# counterMeterFixes.net
KiCad netlist of a schematic drawn in EAGLE
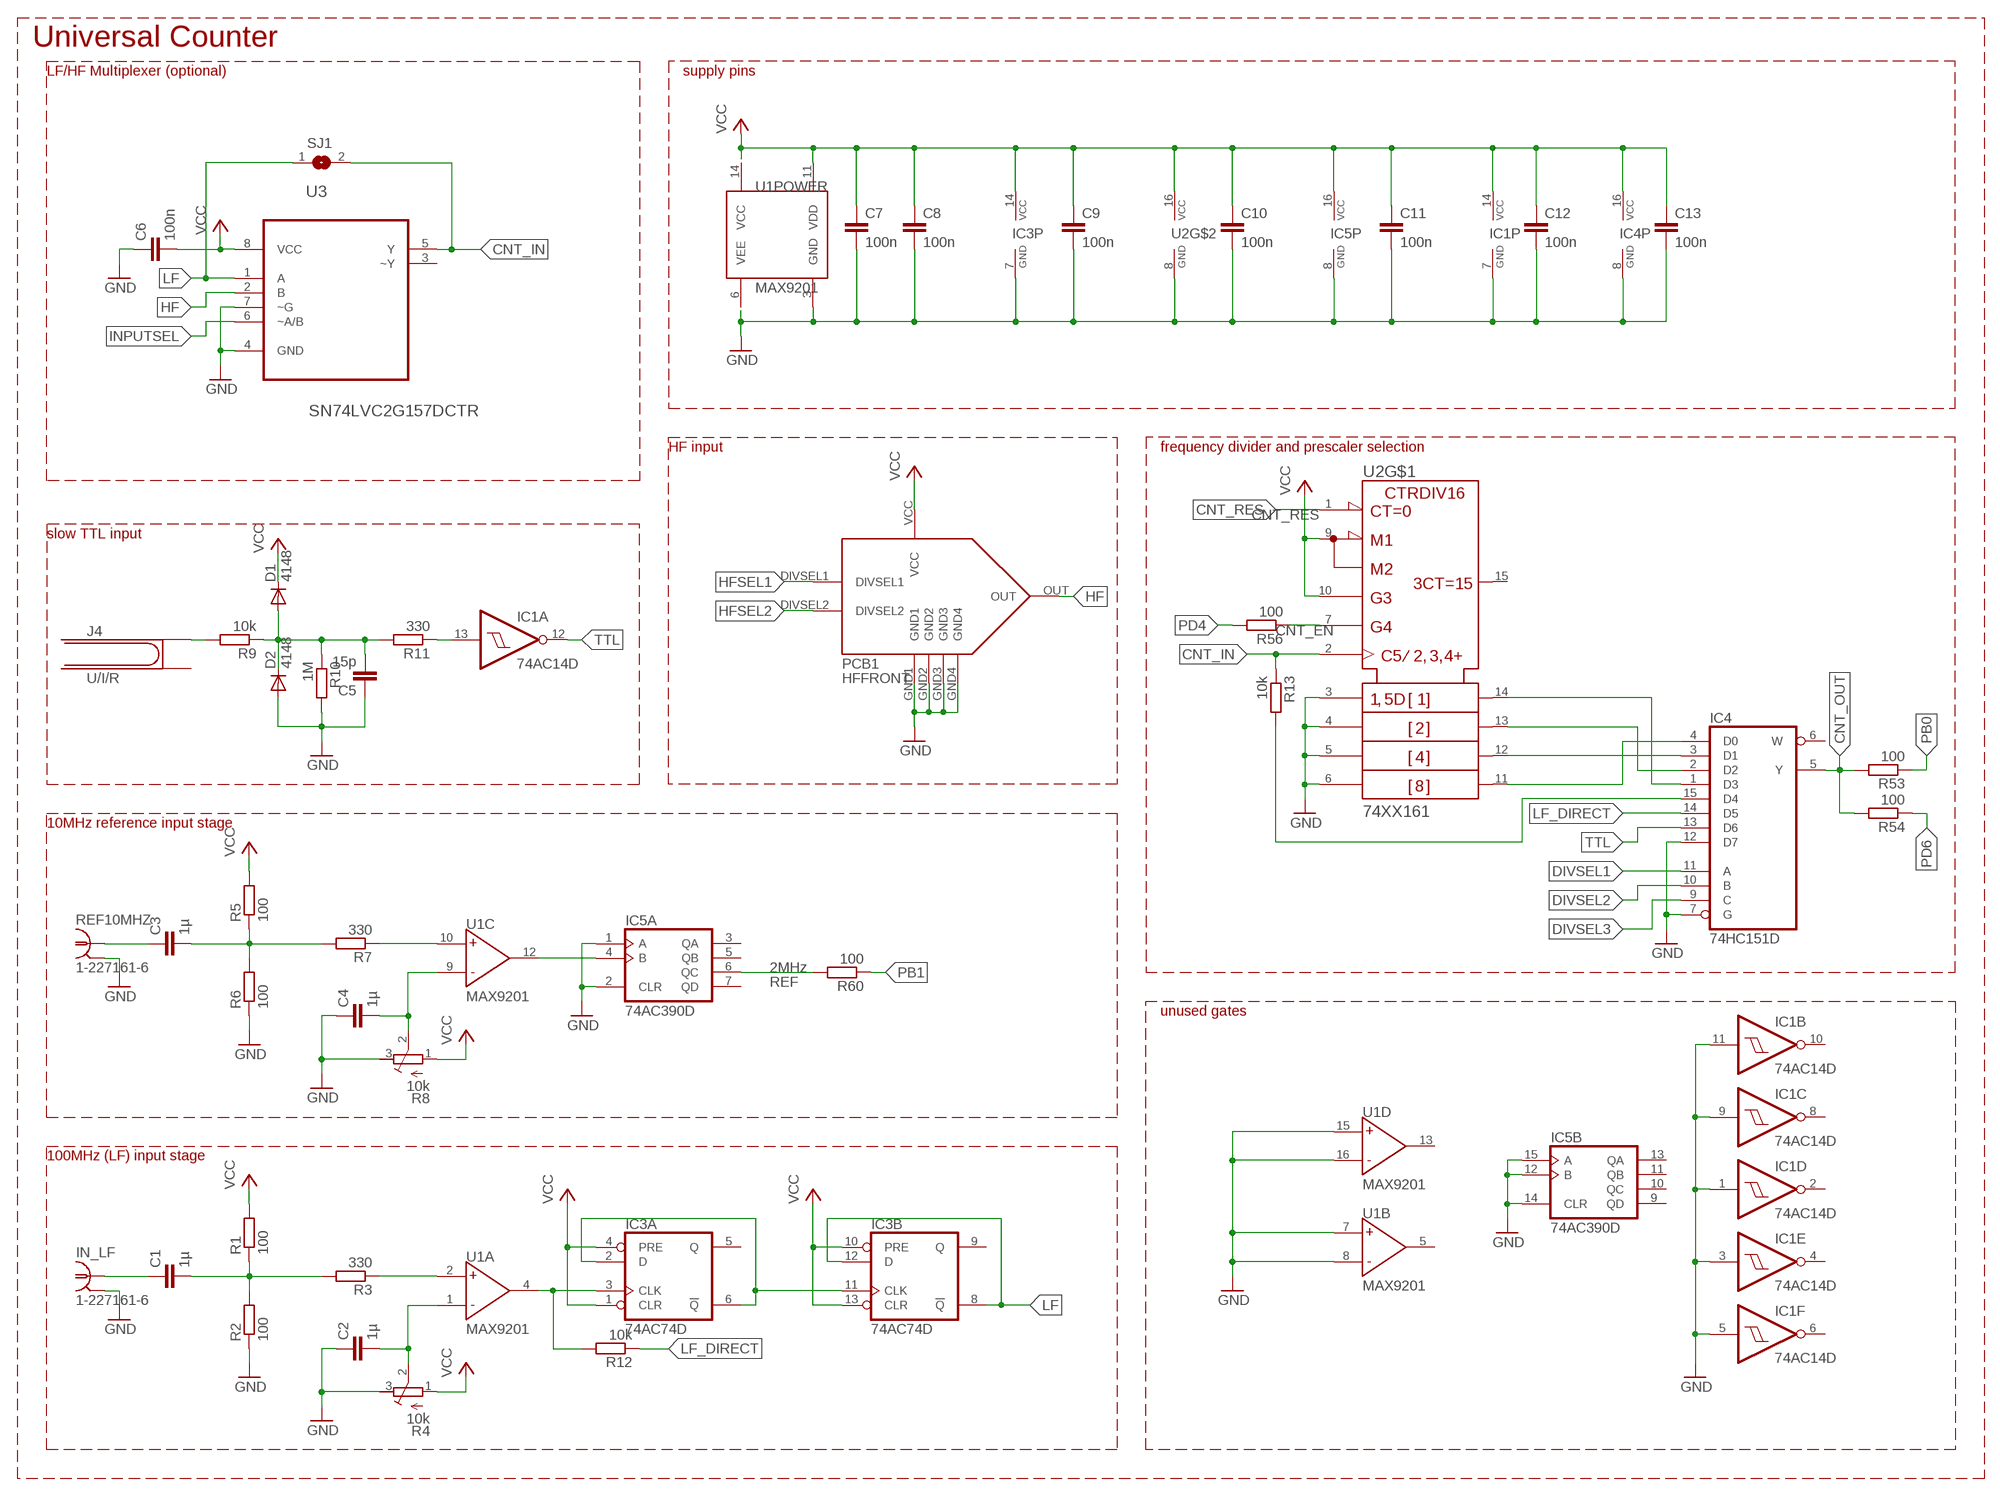
[diagram p0: schematic, sheet 1, part 1 of 2]
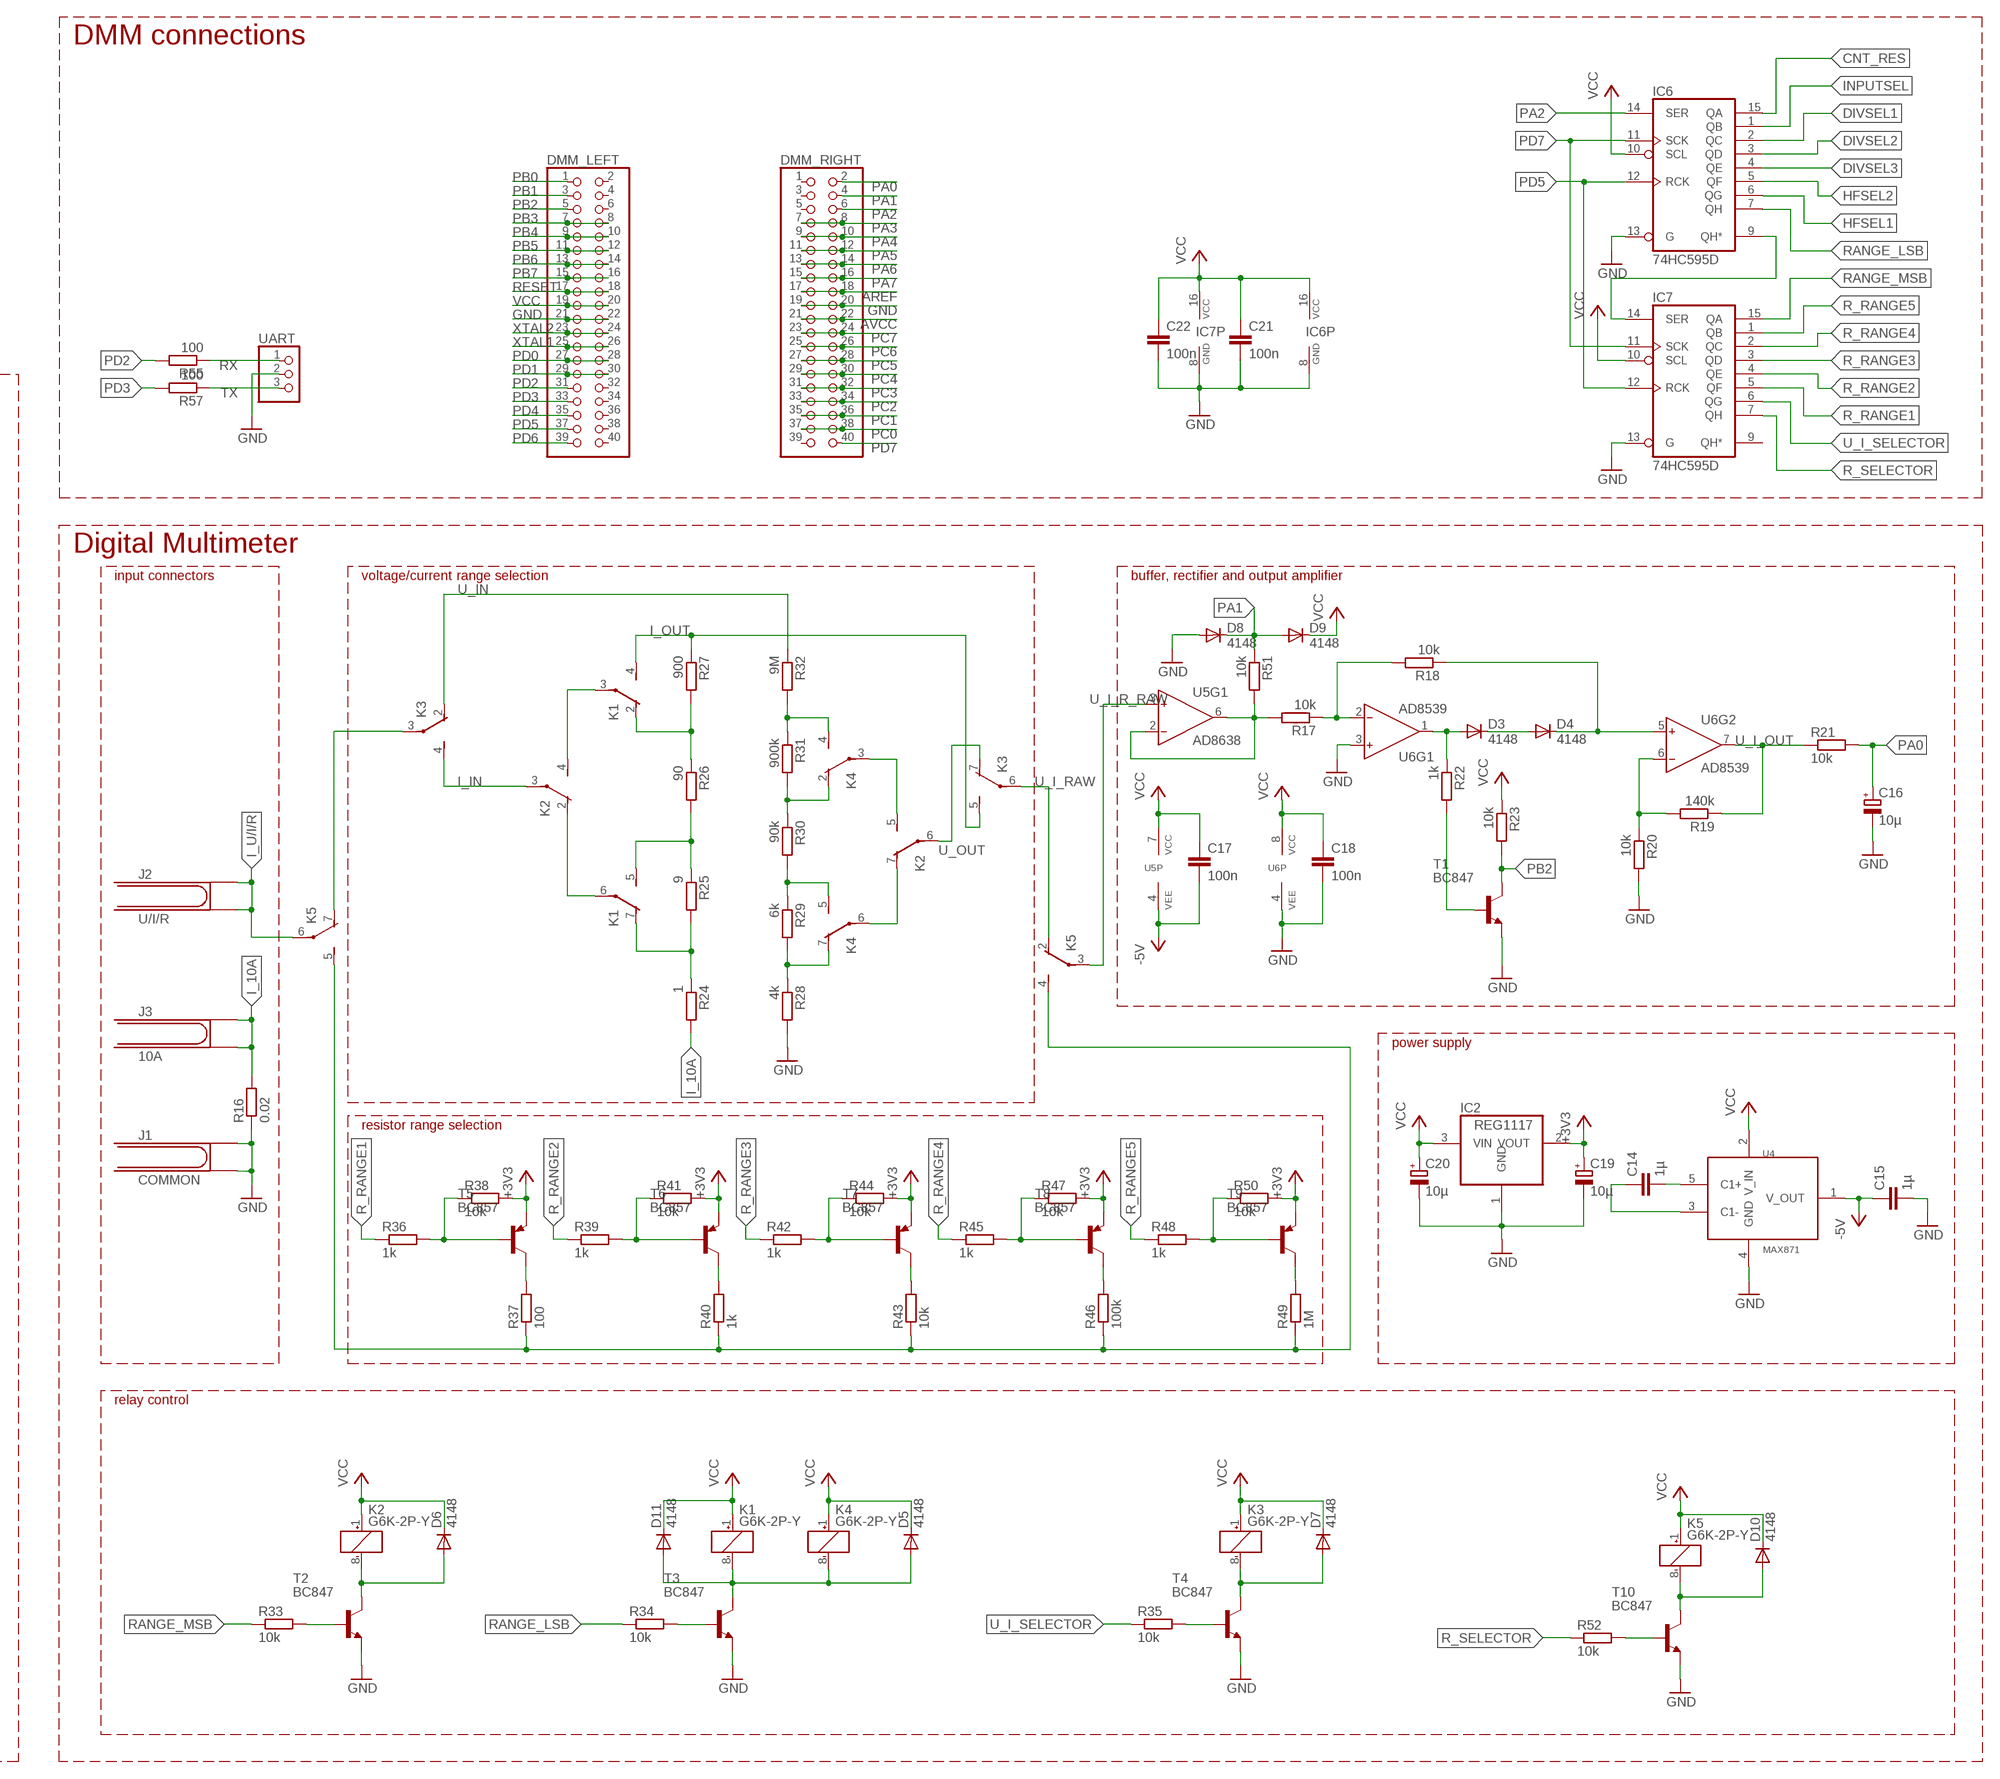
[diagram p1: schematic, sheet 1, part 2 of 2]

(export (version "E")
  (design (tool "Eeschema 10.0.6"))
  (components
    (comp (ref "C1")
      (value "1µ")
      (footprint "eagle-import:C0603")
      (libsource (lib "eagle-import") (part "C-EUC0603"))
    )
    (comp (ref "C2")
      (value "1µ")
      (footprint "eagle-import:C0603")
      (libsource (lib "eagle-import") (part "C-EUC0603"))
    )
    (comp (ref "C3")
      (value "1µ")
      (footprint "eagle-import:C0603")
      (libsource (lib "eagle-import") (part "C-EUC0603"))
    )
    (comp (ref "C4")
      (value "1µ")
      (footprint "eagle-import:C0603")
      (libsource (lib "eagle-import") (part "C-EUC0603"))
    )
    (comp (ref "C5")
      (value "15p")
      (footprint "eagle-import:C0603")
      (libsource (lib "eagle-import") (part "C-EUC0603"))
    )
    (comp (ref "C6")
      (value "100n")
      (footprint "eagle-import:C0603")
      (libsource (lib "eagle-import") (part "C-EUC0603"))
    )
    (comp (ref "C7")
      (value "100n")
      (footprint "eagle-import:C0603")
      (libsource (lib "eagle-import") (part "C-EUC0603"))
    )
    (comp (ref "C8")
      (value "100n")
      (footprint "eagle-import:C0603")
      (libsource (lib "eagle-import") (part "C-EUC0603"))
    )
    (comp (ref "C9")
      (value "100n")
      (footprint "eagle-import:C0603")
      (libsource (lib "eagle-import") (part "C-EUC0603"))
    )
    (comp (ref "C10")
      (value "100n")
      (footprint "eagle-import:C0603")
      (libsource (lib "eagle-import") (part "C-EUC0603"))
    )
    (comp (ref "C11")
      (value "100n")
      (footprint "eagle-import:C0603")
      (libsource (lib "eagle-import") (part "C-EUC0603"))
    )
    (comp (ref "C12")
      (value "100n")
      (footprint "eagle-import:C0603")
      (libsource (lib "eagle-import") (part "C-EUC0603"))
    )
    (comp (ref "C13")
      (value "100n")
      (footprint "eagle-import:C0603")
      (libsource (lib "eagle-import") (part "C-EUC0603"))
    )
    (comp (ref "C14")
      (value "1µ")
      (footprint "eagle-import:C0603")
      (libsource (lib "eagle-import") (part "C-EUC0603"))
    )
    (comp (ref "C15")
      (value "1µ")
      (footprint "eagle-import:C0603")
      (libsource (lib "eagle-import") (part "C-EUC0603"))
    )
    (comp (ref "C16")
      (value "10µ")
      (footprint "eagle-import:E2-5")
      (libsource (lib "eagle-import") (part "CPOL-EUE2-5"))
    )
    (comp (ref "C17")
      (value "100n")
      (footprint "eagle-import:C0603")
      (libsource (lib "eagle-import") (part "C-EUC0603"))
    )
    (comp (ref "C18")
      (value "100n")
      (footprint "eagle-import:C0603")
      (libsource (lib "eagle-import") (part "C-EUC0603"))
    )
    (comp (ref "C19")
      (value "10µ")
      (footprint "eagle-import:E2-5")
      (libsource (lib "eagle-import") (part "CPOL-EUE2-5"))
    )
    (comp (ref "C20")
      (value "10µ")
      (footprint "eagle-import:E2-5")
      (libsource (lib "eagle-import") (part "CPOL-EUE2-5"))
    )
    (comp (ref "C21")
      (value "100n")
      (footprint "eagle-import:C0603")
      (libsource (lib "eagle-import") (part "C-EUC0603"))
    )
    (comp (ref "C22")
      (value "100n")
      (footprint "eagle-import:C0603")
      (libsource (lib "eagle-import") (part "C-EUC0603"))
    )
    (comp (ref "D1")
      (value "4148")
      (footprint "eagle-import:SOD323-W")
      (libsource (lib "eagle-import") (part "DIODE-SOD323-W"))
    )
    (comp (ref "D2")
      (value "4148")
      (footprint "eagle-import:SOD323-W")
      (libsource (lib "eagle-import") (part "DIODE-SOD323-W"))
    )
    (comp (ref "D3")
      (value "4148")
      (footprint "eagle-import:SOD323-W")
      (libsource (lib "eagle-import") (part "DIODE-SOD323-W"))
    )
    (comp (ref "D4")
      (value "4148")
      (footprint "eagle-import:SOD323-W")
      (libsource (lib "eagle-import") (part "DIODE-SOD323-W"))
    )
    (comp (ref "D5")
      (value "4148")
      (footprint "eagle-import:SOD323-W")
      (libsource (lib "eagle-import") (part "DIODE-SOD323-W"))
    )
    (comp (ref "D6")
      (value "4148")
      (footprint "eagle-import:SOD323-W")
      (libsource (lib "eagle-import") (part "DIODE-SOD323-W"))
    )
    (comp (ref "D7")
      (value "4148")
      (footprint "eagle-import:SOD323-W")
      (libsource (lib "eagle-import") (part "DIODE-SOD323-W"))
    )
    (comp (ref "D8")
      (value "4148")
      (footprint "eagle-import:SOD323-W")
      (libsource (lib "eagle-import") (part "DIODE-SOD323-W"))
    )
    (comp (ref "D9")
      (value "4148")
      (footprint "eagle-import:SOD323-W")
      (libsource (lib "eagle-import") (part "DIODE-SOD323-W"))
    )
    (comp (ref "D10")
      (value "4148")
      (footprint "eagle-import:SOD323-W")
      (libsource (lib "eagle-import") (part "DIODE-SOD323-W"))
    )
    (comp (ref "D11")
      (value "4148")
      (footprint "eagle-import:SOD323-W")
      (libsource (lib "eagle-import") (part "DIODE-SOD323-W"))
    )
    (comp (ref "DMM_LEFT")
      (value "PINHD-2X20")
      (footprint "eagle-import:2X20")
      (libsource (lib "eagle-import") (part "PINHD-2X20"))
    )
    (comp (ref "DMM_RIGHT")
      (value "PINHD-2X20")
      (footprint "eagle-import:2X20")
      (libsource (lib "eagle-import") (part "PINHD-2X20"))
    )
    (comp (ref "IC1")
      (value "74AC14D")
      (footprint "eagle-import:SO14")
      (libsource (lib "eagle-import") (part "7414DAC"))
    )
    (comp (ref "IC2")
      (value "REG1117")
      (footprint "eagle-import:SOT223")
      (libsource (lib "eagle-import") (part "REG1117"))
    )
    (comp (ref "IC3")
      (value "74AC74D")
      (footprint "eagle-import:SO14")
      (libsource (lib "eagle-import") (part "7474DAC"))
    )
    (comp (ref "IC4")
      (value "74HC151D")
      (footprint "eagle-import:SO16")
      (libsource (lib "eagle-import") (part "74151DHC"))
    )
    (comp (ref "IC5")
      (value "74AC390D")
      (footprint "eagle-import:SO16")
      (libsource (lib "eagle-import") (part "74390DAC"))
    )
    (comp (ref "IC6")
      (value "74HC595D")
      (footprint "eagle-import:SO16")
      (libsource (lib "eagle-import") (part "74595DHC"))
    )
    (comp (ref "IC7")
      (value "74HC595D")
      (footprint "eagle-import:SO16")
      (libsource (lib "eagle-import") (part "74595DHC"))
    )
    (comp (ref "IN_LF")
      (value "1-227161-6")
      (footprint "eagle-import:AMP_227161")
      (fields (field (name "MF") "TYCO ELECTRONICS"))
      (libsource (lib "eagle-import") (part "?2271611--6"))
    )
    (comp (ref "J1")
      (value "COMMON")
      (footprint "eagle-import:4MMJACK")
      (libsource (lib "eagle-import") (part "4MMJACK"))
    )
    (comp (ref "J2")
      (value "U/I/R")
      (footprint "eagle-import:4MMJACK")
      (libsource (lib "eagle-import") (part "4MMJACK"))
    )
    (comp (ref "J3")
      (value "10A")
      (footprint "eagle-import:4MMJACK")
      (libsource (lib "eagle-import") (part "4MMJACK"))
    )
    (comp (ref "J4")
      (value "U/I/R")
      (footprint "eagle-import:4MMJACK")
      (libsource (lib "eagle-import") (part "4MMJACK"))
    )
    (comp (ref "K1")
      (value "G6K-2P-Y")
      (footprint "eagle-import:G6K-2P-Y")
      (fields (field (name "MF") "OMRON COMPONENTS USA") (field (name "MPN") "G6K-2P-Y DC12"))
      (libsource (lib "eagle-import") (part "G6K-2P-Y"))
    )
    (comp (ref "K2")
      (value "G6K-2P-Y")
      (footprint "eagle-import:G6K-2P-Y")
      (fields (field (name "MF") "OMRON COMPONENTS USA") (field (name "MPN") "G6K-2P-Y DC12"))
      (libsource (lib "eagle-import") (part "G6K-2P-Y"))
    )
    (comp (ref "K3")
      (value "G6K-2P-Y")
      (footprint "eagle-import:G6K-2P-Y")
      (fields (field (name "MF") "OMRON COMPONENTS USA") (field (name "MPN") "G6K-2P-Y DC12"))
      (libsource (lib "eagle-import") (part "G6K-2P-Y"))
    )
    (comp (ref "K4")
      (value "G6K-2P-Y")
      (footprint "eagle-import:G6K-2P-Y")
      (fields (field (name "MF") "OMRON COMPONENTS USA") (field (name "MPN") "G6K-2P-Y DC12"))
      (libsource (lib "eagle-import") (part "G6K-2P-Y"))
    )
    (comp (ref "K5")
      (value "G6K-2P-Y")
      (footprint "eagle-import:G6K-2P-Y")
      (fields (field (name "MF") "OMRON COMPONENTS USA") (field (name "MPN") "G6K-2P-Y DC12"))
      (libsource (lib "eagle-import") (part "G6K-2P-Y"))
    )
    (comp (ref "PCB1")
      (value "HFFRONT")
      (footprint "eagle-import:HFFRONT")
      (libsource (lib "eagle-import") (part "HFFRONT"))
    )
    (comp (ref "R1")
      (value "100")
      (footprint "eagle-import:R0603")
      (libsource (lib "eagle-import") (part "R-EU_R0603"))
    )
    (comp (ref "R2")
      (value "100")
      (footprint "eagle-import:R0603")
      (libsource (lib "eagle-import") (part "R-EU_R0603"))
    )
    (comp (ref "R3")
      (value "330")
      (footprint "eagle-import:R0603")
      (libsource (lib "eagle-import") (part "R-EU_R0603"))
    )
    (comp (ref "R4")
      (value "10k")
      (footprint "eagle-import:RTRIM64W")
      (libsource (lib "eagle-import") (part "R-TRIMM64W"))
    )
    (comp (ref "R5")
      (value "100")
      (footprint "eagle-import:R0603")
      (libsource (lib "eagle-import") (part "R-EU_R0603"))
    )
    (comp (ref "R6")
      (value "100")
      (footprint "eagle-import:R0603")
      (libsource (lib "eagle-import") (part "R-EU_R0603"))
    )
    (comp (ref "R7")
      (value "330")
      (footprint "eagle-import:R0603")
      (libsource (lib "eagle-import") (part "R-EU_R0603"))
    )
    (comp (ref "R8")
      (value "10k")
      (footprint "eagle-import:RTRIM64W")
      (libsource (lib "eagle-import") (part "R-TRIMM64W"))
    )
    (comp (ref "R9")
      (value "10k")
      (footprint "eagle-import:R0603")
      (libsource (lib "eagle-import") (part "R-EU_R0603"))
    )
    (comp (ref "R10")
      (value "1M")
      (footprint "eagle-import:R0603")
      (libsource (lib "eagle-import") (part "R-EU_R0603"))
    )
    (comp (ref "R11")
      (value "330")
      (footprint "eagle-import:R0603")
      (libsource (lib "eagle-import") (part "R-EU_R0603"))
    )
    (comp (ref "R12")
      (value "10k")
      (footprint "eagle-import:R0603")
      (libsource (lib "eagle-import") (part "R-EU_R0603"))
    )
    (comp (ref "R13")
      (value "10k")
      (footprint "eagle-import:R0603")
      (libsource (lib "eagle-import") (part "R-EU_R0603"))
    )
    (comp (ref "R16")
      (value "0.02")
      (footprint "eagle-import:R2512")
      (libsource (lib "eagle-import") (part "R-EU_R2512"))
    )
    (comp (ref "R17")
      (value "10k")
      (footprint "eagle-import:R0603")
      (libsource (lib "eagle-import") (part "R-EU_R0603"))
    )
    (comp (ref "R18")
      (value "10k")
      (footprint "eagle-import:R0603")
      (libsource (lib "eagle-import") (part "R-EU_R0603"))
    )
    (comp (ref "R19")
      (value "140k")
      (footprint "eagle-import:R0603")
      (libsource (lib "eagle-import") (part "R-EU_R0603"))
    )
    (comp (ref "R20")
      (value "10k")
      (footprint "eagle-import:R0603")
      (libsource (lib "eagle-import") (part "R-EU_R0603"))
    )
    (comp (ref "R21")
      (value "10k")
      (footprint "eagle-import:R0603")
      (libsource (lib "eagle-import") (part "R-EU_R0603"))
    )
    (comp (ref "R22")
      (value "1k")
      (footprint "eagle-import:R0603")
      (libsource (lib "eagle-import") (part "R-EU_R0603"))
    )
    (comp (ref "R23")
      (value "10k")
      (footprint "eagle-import:R0603")
      (libsource (lib "eagle-import") (part "R-EU_R0603"))
    )
    (comp (ref "R24")
      (value "1")
      (footprint "eagle-import:R0603")
      (libsource (lib "eagle-import") (part "R-EU_R0603"))
    )
    (comp (ref "R25")
      (value "9")
      (footprint "eagle-import:R0603")
      (libsource (lib "eagle-import") (part "R-EU_R0603"))
    )
    (comp (ref "R26")
      (value "90")
      (footprint "eagle-import:R0603")
      (libsource (lib "eagle-import") (part "R-EU_R0603"))
    )
    (comp (ref "R27")
      (value "900")
      (footprint "eagle-import:R0603")
      (libsource (lib "eagle-import") (part "R-EU_R0603"))
    )
    (comp (ref "R28")
      (value "4k")
      (footprint "eagle-import:R0603")
      (libsource (lib "eagle-import") (part "R-EU_R0603"))
    )
    (comp (ref "R29")
      (value "6k")
      (footprint "eagle-import:R0603")
      (libsource (lib "eagle-import") (part "R-EU_R0603"))
    )
    (comp (ref "R30")
      (value "90k")
      (footprint "eagle-import:R0603")
      (libsource (lib "eagle-import") (part "R-EU_R0603"))
    )
    (comp (ref "R31")
      (value "900k")
      (footprint "eagle-import:R0603")
      (libsource (lib "eagle-import") (part "R-EU_R0603"))
    )
    (comp (ref "R32")
      (value "9M")
      (footprint "eagle-import:R0603")
      (libsource (lib "eagle-import") (part "R-EU_R0603"))
    )
    (comp (ref "R33")
      (value "10k")
      (footprint "eagle-import:R0603")
      (libsource (lib "eagle-import") (part "R-EU_R0603"))
    )
    (comp (ref "R34")
      (value "10k")
      (footprint "eagle-import:R0603")
      (libsource (lib "eagle-import") (part "R-EU_R0603"))
    )
    (comp (ref "R35")
      (value "10k")
      (footprint "eagle-import:R0603")
      (libsource (lib "eagle-import") (part "R-EU_R0603"))
    )
    (comp (ref "R36")
      (value "1k")
      (footprint "eagle-import:R0603")
      (libsource (lib "eagle-import") (part "R-EU_R0603"))
    )
    (comp (ref "R37")
      (value "100")
      (footprint "eagle-import:R0603")
      (libsource (lib "eagle-import") (part "R-EU_R0603"))
    )
    (comp (ref "R38")
      (value "10k")
      (footprint "eagle-import:R0603")
      (libsource (lib "eagle-import") (part "R-EU_R0603"))
    )
    (comp (ref "R39")
      (value "1k")
      (footprint "eagle-import:R0603")
      (libsource (lib "eagle-import") (part "R-EU_R0603"))
    )
    (comp (ref "R40")
      (value "1k")
      (footprint "eagle-import:R0603")
      (libsource (lib "eagle-import") (part "R-EU_R0603"))
    )
    (comp (ref "R41")
      (value "10k")
      (footprint "eagle-import:R0603")
      (libsource (lib "eagle-import") (part "R-EU_R0603"))
    )
    (comp (ref "R42")
      (value "1k")
      (footprint "eagle-import:R0603")
      (libsource (lib "eagle-import") (part "R-EU_R0603"))
    )
    (comp (ref "R43")
      (value "10k")
      (footprint "eagle-import:R0603")
      (libsource (lib "eagle-import") (part "R-EU_R0603"))
    )
    (comp (ref "R44")
      (value "10k")
      (footprint "eagle-import:R0603")
      (libsource (lib "eagle-import") (part "R-EU_R0603"))
    )
    (comp (ref "R45")
      (value "1k")
      (footprint "eagle-import:R0603")
      (libsource (lib "eagle-import") (part "R-EU_R0603"))
    )
    (comp (ref "R46")
      (value "100k")
      (footprint "eagle-import:R0603")
      (libsource (lib "eagle-import") (part "R-EU_R0603"))
    )
    (comp (ref "R47")
      (value "10k")
      (footprint "eagle-import:R0603")
      (libsource (lib "eagle-import") (part "R-EU_R0603"))
    )
    (comp (ref "R48")
      (value "1k")
      (footprint "eagle-import:R0603")
      (libsource (lib "eagle-import") (part "R-EU_R0603"))
    )
    (comp (ref "R49")
      (value "1M")
      (footprint "eagle-import:R0603")
      (libsource (lib "eagle-import") (part "R-EU_R0603"))
    )
    (comp (ref "R50")
      (value "10k")
      (footprint "eagle-import:R0603")
      (libsource (lib "eagle-import") (part "R-EU_R0603"))
    )
    (comp (ref "R51")
      (value "10k")
      (footprint "eagle-import:R0603")
      (libsource (lib "eagle-import") (part "R-EU_R0603"))
    )
    (comp (ref "R52")
      (value "10k")
      (footprint "eagle-import:R0603")
      (libsource (lib "eagle-import") (part "R-EU_R0603"))
    )
    (comp (ref "R53")
      (value "100")
      (footprint "eagle-import:R0603")
      (libsource (lib "eagle-import") (part "R-EU_R0603"))
    )
    (comp (ref "R54")
      (value "100")
      (footprint "eagle-import:R0603")
      (libsource (lib "eagle-import") (part "R-EU_R0603"))
    )
    (comp (ref "R55")
      (value "100")
      (footprint "eagle-import:R0603")
      (libsource (lib "eagle-import") (part "R-EU_R0603"))
    )
    (comp (ref "R56")
      (value "100")
      (footprint "eagle-import:R0603")
      (libsource (lib "eagle-import") (part "R-EU_R0603"))
    )
    (comp (ref "R57")
      (value "100")
      (footprint "eagle-import:R0603")
      (libsource (lib "eagle-import") (part "R-EU_R0603"))
    )
    (comp (ref "R60")
      (value "100")
      (footprint "eagle-import:R0603")
      (libsource (lib "eagle-import") (part "R-EU_R0603"))
    )
    (comp (ref "REF10MHZ")
      (value "1-227161-6")
      (footprint "eagle-import:AMP_227161")
      (fields (field (name "MF") "TYCO ELECTRONICS"))
      (libsource (lib "eagle-import") (part "?2271611--6"))
    )
    (comp (ref "SJ1") (value "SJ") (footprint "eagle-import:SJ") (libsource (lib "eagle-import") (part "SJ")))
    (comp (ref "T1")
      (value "BC847")
      (footprint "eagle-import:SOT23")
      (libsource (lib "eagle-import") (part "BC847"))
    )
    (comp (ref "T2")
      (value "BC847")
      (footprint "eagle-import:SOT23")
      (libsource (lib "eagle-import") (part "BC847"))
    )
    (comp (ref "T3")
      (value "BC847")
      (footprint "eagle-import:SOT23")
      (libsource (lib "eagle-import") (part "BC847"))
    )
    (comp (ref "T4")
      (value "BC847")
      (footprint "eagle-import:SOT23")
      (libsource (lib "eagle-import") (part "BC847"))
    )
    (comp (ref "T5")
      (value "BC857")
      (footprint "eagle-import:SOT23-BEC")
      (libsource (lib "eagle-import") (part "-PNP-SOT23-BECBC857C"))
    )
    (comp (ref "T6")
      (value "BC857")
      (footprint "eagle-import:SOT23-BEC")
      (libsource (lib "eagle-import") (part "-PNP-SOT23-BECBC857C"))
    )
    (comp (ref "T7")
      (value "BC857")
      (footprint "eagle-import:SOT23-BEC")
      (libsource (lib "eagle-import") (part "-PNP-SOT23-BECBC857C"))
    )
    (comp (ref "T8")
      (value "BC857")
      (footprint "eagle-import:SOT23-BEC")
      (libsource (lib "eagle-import") (part "-PNP-SOT23-BECBC857C"))
    )
    (comp (ref "T9")
      (value "BC857")
      (footprint "eagle-import:SOT23-BEC")
      (libsource (lib "eagle-import") (part "-PNP-SOT23-BECBC857C"))
    )
    (comp (ref "T10")
      (value "BC847")
      (footprint "eagle-import:SOT23")
      (libsource (lib "eagle-import") (part "BC847"))
    )
    (comp (ref "U1")
      (value "MAX9201")
      (footprint "eagle-import:SOIC16")
      (libsource (lib "eagle-import") (part "MAX9201"))
    )
    (comp (ref "U2")
      (value "74XX161")
      (footprint "eagle-import:SOIC16")
      (libsource (lib "eagle-import") (part "74XX161"))
    )
    (comp (ref "U3")
      (value "SN74LVC2G157DCTR")
      (footprint "eagle-import:SOP65P400X130-8N")
      (libsource (lib "eagle-import") (part "SN74LVC2G157DCTR"))
    )
    (comp (ref "U4")
      (value "MAX871")
      (footprint "eagle-import:SOT23-5")
      (libsource (lib "eagle-import") (part "MAX871"))
    )
    (comp (ref "U5")
      (value "AD8638")
      (footprint "eagle-import:SOIC8")
      (libsource (lib "eagle-import") (part "AD8638"))
    )
    (comp (ref "U6")
      (value "AD8539")
      (footprint "eagle-import:SOIC8")
      (libsource (lib "eagle-import") (part "AD8539"))
    )
    (comp (ref "UART")
      (value "PINHD-1X3")
      (footprint "eagle-import:1X03")
      (libsource (lib "eagle-import") (part "PINHD-1X3"))
    )
  )
  (nets
    (net (code "1") (name "+3V3") (class "Default")
      (node (ref "C19") (pin "+") (pinfunction "+_+") (pintype "passive"))
      (node (ref "IC2") (pin "2") (pinfunction "VOUT_2") (pintype "output"))
      (node (ref "R38") (pin "2") (pinfunction "2_2") (pintype "passive"))
      (node (ref "R41") (pin "2") (pinfunction "2_2") (pintype "passive"))
      (node (ref "R44") (pin "2") (pinfunction "2_2") (pintype "passive"))
      (node (ref "R47") (pin "2") (pinfunction "2_2") (pintype "passive"))
      (node (ref "R50") (pin "2") (pinfunction "2_2") (pintype "passive"))
      (node (ref "T5") (pin "E") (pinfunction "E_E") (pintype "passive"))
      (node (ref "T6") (pin "E") (pinfunction "E_E") (pintype "passive"))
      (node (ref "T7") (pin "E") (pinfunction "E_E") (pintype "passive"))
      (node (ref "T8") (pin "E") (pinfunction "E_E") (pintype "passive"))
      (node (ref "T9") (pin "E") (pinfunction "E_E") (pintype "passive"))
    )
    (net (code "2") (name "-5V") (class "Default")
      (node (ref "C15") (pin "1") (pinfunction "1_1") (pintype "passive"))
      (node (ref "C17") (pin "2") (pinfunction "2_2") (pintype "passive"))
      (node (ref "U4") (pin "1") (pinfunction "V_OUT_1") (pintype "bidirectional"))
      (node (ref "U5") (pin "4") (pinfunction "VEE_4") (pintype "bidirectional"))
    )
    (net (code "3") (name "/AREF") (class "Default")
      (node (ref "DMM_RIGHT") (pin "17") (pinfunction "17_17") (pintype "passive"))
      (node (ref "DMM_RIGHT") (pin "18") (pinfunction "18_18") (pintype "passive"))
    )
    (net (code "4") (name "/AVCC") (class "Default")
      (node (ref "DMM_RIGHT") (pin "21") (pinfunction "21_21") (pintype "passive"))
      (node (ref "DMM_RIGHT") (pin "22") (pinfunction "22_22") (pintype "passive"))
    )
    (net (code "5") (name "/CNT_EN") (class "Default")
      (node (ref "R56") (pin "1") (pinfunction "1_1") (pintype "passive"))
      (node (ref "U2") (pin "7") (pinfunction "ENP_7") (pintype "input"))
    )
    (net (code "6") (name "/I_IN") (class "Default")
      (node (ref "K2") (pin "3") (pinfunction "P_3") (pintype "passive"))
      (node (ref "K3") (pin "4") (pinfunction "S_4") (pintype "passive"))
    )
    (net (code "7") (name "/I_OUT") (class "Default")
      (node (ref "K1") (pin "4") (pinfunction "S_4") (pintype "passive"))
      (node (ref "K3") (pin "5") (pinfunction "S_5") (pintype "passive"))
      (node (ref "R27") (pin "1") (pinfunction "1_1") (pintype "passive"))
    )
    (net (code "8") (name "/PA3") (class "Default")
      (node (ref "DMM_RIGHT") (pin "7") (pinfunction "7_7") (pintype "passive"))
      (node (ref "DMM_RIGHT") (pin "8") (pinfunction "8_8") (pintype "passive"))
    )
    (net (code "9") (name "/PA4") (class "Default")
      (node (ref "DMM_RIGHT") (pin "10") (pinfunction "10_10") (pintype "passive"))
      (node (ref "DMM_RIGHT") (pin "9") (pinfunction "9_9") (pintype "passive"))
    )
    (net (code "10") (name "/PA5") (class "Default")
      (node (ref "DMM_RIGHT") (pin "11") (pinfunction "11_11") (pintype "passive"))
      (node (ref "DMM_RIGHT") (pin "12") (pinfunction "12_12") (pintype "passive"))
    )
    (net (code "11") (name "/PA6") (class "Default")
      (node (ref "DMM_RIGHT") (pin "13") (pinfunction "13_13") (pintype "passive"))
      (node (ref "DMM_RIGHT") (pin "14") (pinfunction "14_14") (pintype "passive"))
    )
    (net (code "12") (name "/PA7") (class "Default")
      (node (ref "DMM_RIGHT") (pin "15") (pinfunction "15_15") (pintype "passive"))
      (node (ref "DMM_RIGHT") (pin "16") (pinfunction "16_16") (pintype "passive"))
    )
    (net (code "13") (name "/PB3") (class "Default")
      (node (ref "DMM_LEFT") (pin "7") (pinfunction "7_7") (pintype "passive"))
      (node (ref "DMM_LEFT") (pin "8") (pinfunction "8_8") (pintype "passive"))
    )
    (net (code "14") (name "/PB4") (class "Default")
      (node (ref "DMM_LEFT") (pin "10") (pinfunction "10_10") (pintype "passive"))
      (node (ref "DMM_LEFT") (pin "9") (pinfunction "9_9") (pintype "passive"))
    )
    (net (code "15") (name "/PB5") (class "Default")
      (node (ref "DMM_LEFT") (pin "11") (pinfunction "11_11") (pintype "passive"))
      (node (ref "DMM_LEFT") (pin "12") (pinfunction "12_12") (pintype "passive"))
    )
    (net (code "16") (name "/PB6") (class "Default")
      (node (ref "DMM_LEFT") (pin "13") (pinfunction "13_13") (pintype "passive"))
      (node (ref "DMM_LEFT") (pin "14") (pinfunction "14_14") (pintype "passive"))
    )
    (net (code "17") (name "/PB7") (class "Default")
      (node (ref "DMM_LEFT") (pin "15") (pinfunction "15_15") (pintype "passive"))
      (node (ref "DMM_LEFT") (pin "16") (pinfunction "16_16") (pintype "passive"))
    )
    (net (code "18") (name "/PC0") (class "Default")
      (node (ref "DMM_RIGHT") (pin "37") (pinfunction "37_37") (pintype "passive"))
      (node (ref "DMM_RIGHT") (pin "38") (pinfunction "38_38") (pintype "passive"))
    )
    (net (code "19") (name "/PC1") (class "Default")
      (node (ref "DMM_RIGHT") (pin "35") (pinfunction "35_35") (pintype "passive"))
      (node (ref "DMM_RIGHT") (pin "36") (pinfunction "36_36") (pintype "passive"))
    )
    (net (code "20") (name "/PC2") (class "Default")
      (node (ref "DMM_RIGHT") (pin "33") (pinfunction "33_33") (pintype "passive"))
      (node (ref "DMM_RIGHT") (pin "34") (pinfunction "34_34") (pintype "passive"))
    )
    (net (code "21") (name "/PC3") (class "Default")
      (node (ref "DMM_RIGHT") (pin "31") (pinfunction "31_31") (pintype "passive"))
      (node (ref "DMM_RIGHT") (pin "32") (pinfunction "32_32") (pintype "passive"))
    )
    (net (code "22") (name "/PC4") (class "Default")
      (node (ref "DMM_RIGHT") (pin "29") (pinfunction "29_29") (pintype "passive"))
      (node (ref "DMM_RIGHT") (pin "30") (pinfunction "30_30") (pintype "passive"))
    )
    (net (code "23") (name "/PC5") (class "Default")
      (node (ref "DMM_RIGHT") (pin "27") (pinfunction "27_27") (pintype "passive"))
      (node (ref "DMM_RIGHT") (pin "28") (pinfunction "28_28") (pintype "passive"))
    )
    (net (code "24") (name "/PC6") (class "Default")
      (node (ref "DMM_RIGHT") (pin "25") (pinfunction "25_25") (pintype "passive"))
      (node (ref "DMM_RIGHT") (pin "26") (pinfunction "26_26") (pintype "passive"))
    )
    (net (code "25") (name "/PC7") (class "Default")
      (node (ref "DMM_RIGHT") (pin "23") (pinfunction "23_23") (pintype "passive"))
      (node (ref "DMM_RIGHT") (pin "24") (pinfunction "24_24") (pintype "passive"))
    )
    (net (code "26") (name "/PD0") (class "Default")
      (node (ref "DMM_LEFT") (pin "27") (pinfunction "27_27") (pintype "passive"))
      (node (ref "DMM_LEFT") (pin "28") (pinfunction "28_28") (pintype "passive"))
    )
    (net (code "27") (name "/PD1") (class "Default")
      (node (ref "DMM_LEFT") (pin "29") (pinfunction "29_29") (pintype "passive"))
      (node (ref "DMM_LEFT") (pin "30") (pinfunction "30_30") (pintype "passive"))
    )
    (net (code "28") (name "/REF") (class "Default")
      (node (ref "IC5") (pin "6") (pinfunction "QC_6") (pintype "output"))
      (node (ref "R60") (pin "2") (pinfunction "2_2") (pintype "passive"))
    )
    (net (code "29") (name "/RESET") (class "Default")
      (node (ref "DMM_LEFT") (pin "17") (pinfunction "17_17") (pintype "passive"))
      (node (ref "DMM_LEFT") (pin "18") (pinfunction "18_18") (pintype "passive"))
    )
    (net (code "30") (name "/RX") (class "Default")
      (node (ref "R55") (pin "1") (pinfunction "1_1") (pintype "passive"))
      (node (ref "UART") (pin "1") (pinfunction "1_1") (pintype "passive"))
    )
    (net (code "31") (name "/TX") (class "Default")
      (node (ref "R57") (pin "1") (pinfunction "1_1") (pintype "passive"))
      (node (ref "UART") (pin "3") (pinfunction "3_3") (pintype "passive"))
    )
    (net (code "32") (name "/U_IN") (class "Default")
      (node (ref "K3") (pin "2") (pinfunction "O_2") (pintype "passive"))
      (node (ref "R32") (pin "1") (pinfunction "1_1") (pintype "passive"))
    )
    (net (code "33") (name "/U_I_OUT") (class "Default")
      (node (ref "R19") (pin "1") (pinfunction "1_1") (pintype "passive"))
      (node (ref "R21") (pin "1") (pinfunction "1_1") (pintype "passive"))
      (node (ref "U6") (pin "7") (pinfunction "OUT_7") (pintype "output"))
    )
    (net (code "34") (name "/U_I_RAW") (class "Default")
      (node (ref "K3") (pin "6") (pinfunction "P_6") (pintype "passive"))
      (node (ref "K5") (pin "2") (pinfunction "O_2") (pintype "passive"))
    )
    (net (code "35") (name "/U_I_R_RAW") (class "Default")
      (node (ref "K5") (pin "3") (pinfunction "P_3") (pintype "passive"))
      (node (ref "U5") (pin "3") (pinfunction "IN+_3") (pintype "input"))
    )
    (net (code "36") (name "/U_OUT") (class "Default")
      (node (ref "K2") (pin "6") (pinfunction "P_6") (pintype "passive"))
      (node (ref "K3") (pin "7") (pinfunction "O_7") (pintype "passive"))
    )
    (net (code "37") (name "/XTAL1") (class "Default")
      (node (ref "DMM_LEFT") (pin "25") (pinfunction "25_25") (pintype "passive"))
      (node (ref "DMM_LEFT") (pin "26") (pinfunction "26_26") (pintype "passive"))
    )
    (net (code "38") (name "/XTAL2") (class "Default")
      (node (ref "DMM_LEFT") (pin "23") (pinfunction "23_23") (pintype "passive"))
      (node (ref "DMM_LEFT") (pin "24") (pinfunction "24_24") (pintype "passive"))
    )
    (net (code "39") (name "CNT_IN") (class "Default")
      (node (ref "R13") (pin "1") (pinfunction "1_1") (pintype "passive"))
      (node (ref "SJ1") (pin "2") (pinfunction "2_2") (pintype "passive"))
      (node (ref "U2") (pin "2") (pinfunction "CLK_2") (pintype "input"))
      (node (ref "U3") (pin "5") (pinfunction "Y_5") (pintype "output"))
    )
    (net (code "40") (name "CNT_OUT") (class "Default")
      (node (ref "IC4") (pin "5") (pinfunction "Y_5") (pintype "output"))
      (node (ref "R53") (pin "2") (pinfunction "2_2") (pintype "passive"))
      (node (ref "R54") (pin "2") (pinfunction "2_2") (pintype "passive"))
    )
    (net (code "41") (name "CNT_RES") (class "Default")
      (node (ref "IC6") (pin "15") (pinfunction "QA_15") (pintype "tri_state"))
      (node (ref "U2") (pin "1") (pinfunction "~{CLR}_1") (pintype "input"))
    )
    (net (code "42") (name "DIVSEL1") (class "Default")
      (node (ref "IC4") (pin "11") (pinfunction "A_11") (pintype "input"))
      (node (ref "IC6") (pin "2") (pinfunction "QC_2") (pintype "tri_state"))
    )
    (net (code "43") (name "DIVSEL2") (class "Default")
      (node (ref "IC4") (pin "10") (pinfunction "B_10") (pintype "input"))
      (node (ref "IC6") (pin "3") (pinfunction "QD_3") (pintype "tri_state"))
    )
    (net (code "44") (name "DIVSEL3") (class "Default")
      (node (ref "IC4") (pin "9") (pinfunction "C_9") (pintype "input"))
      (node (ref "IC6") (pin "4") (pinfunction "QE_4") (pintype "tri_state"))
    )
    (net (code "45") (name "GND") (class "Default")
      (node (ref "C10") (pin "2") (pinfunction "2_2") (pintype "passive"))
      (node (ref "C11") (pin "2") (pinfunction "2_2") (pintype "passive"))
      (node (ref "C12") (pin "2") (pinfunction "2_2") (pintype "passive"))
      (node (ref "C13") (pin "2") (pinfunction "2_2") (pintype "passive"))
      (node (ref "C15") (pin "2") (pinfunction "2_2") (pintype "passive"))
      (node (ref "C16") (pin "-") (pinfunction "-_-") (pintype "passive"))
      (node (ref "C18") (pin "2") (pinfunction "2_2") (pintype "passive"))
      (node (ref "C19") (pin "-") (pinfunction "-_-") (pintype "passive"))
      (node (ref "C2") (pin "1") (pinfunction "1_1") (pintype "passive"))
      (node (ref "C20") (pin "-") (pinfunction "-_-") (pintype "passive"))
      (node (ref "C21") (pin "2") (pinfunction "2_2") (pintype "passive"))
      (node (ref "C22") (pin "2") (pinfunction "2_2") (pintype "passive"))
      (node (ref "C4") (pin "1") (pinfunction "1_1") (pintype "passive"))
      (node (ref "C5") (pin "1") (pinfunction "1_1") (pintype "passive"))
      (node (ref "C6") (pin "1") (pinfunction "1_1") (pintype "passive"))
      (node (ref "C7") (pin "2") (pinfunction "2_2") (pintype "passive"))
      (node (ref "C8") (pin "2") (pinfunction "2_2") (pintype "passive"))
      (node (ref "C9") (pin "2") (pinfunction "2_2") (pintype "passive"))
      (node (ref "D2") (pin "A") (pinfunction "A_A") (pintype "passive"))
      (node (ref "D8") (pin "A") (pinfunction "A_A") (pintype "passive"))
      (node (ref "DMM_LEFT") (pin "21") (pinfunction "21_21") (pintype "passive"))
      (node (ref "DMM_LEFT") (pin "22") (pinfunction "22_22") (pintype "passive"))
      (node (ref "DMM_RIGHT") (pin "19") (pinfunction "19_19") (pintype "passive"))
      (node (ref "DMM_RIGHT") (pin "20") (pinfunction "20_20") (pintype "passive"))
      (node (ref "IC1") (pin "1") (pinfunction "I_1") (pintype "input"))
      (node (ref "IC1") (pin "11") (pinfunction "I_11") (pintype "input"))
      (node (ref "IC1") (pin "3") (pinfunction "I_3") (pintype "input"))
      (node (ref "IC1") (pin "5") (pinfunction "I_5") (pintype "input"))
      (node (ref "IC1") (pin "7") (pinfunction "GND_7") (pintype "power_in"))
      (node (ref "IC1") (pin "9") (pinfunction "I_9") (pintype "input"))
      (node (ref "IC2") (pin "1") (pinfunction "GND_1") (pintype "power_in"))
      (node (ref "IC3") (pin "7") (pinfunction "GND_7") (pintype "power_in"))
      (node (ref "IC4") (pin "12") (pinfunction "D7_12") (pintype "input"))
      (node (ref "IC4") (pin "7") (pinfunction "G_7") (pintype "input"))
      (node (ref "IC4") (pin "8") (pinfunction "GND_8") (pintype "power_in"))
      (node (ref "IC5") (pin "1") (pinfunction "A_1") (pintype "input"))
      (node (ref "IC5") (pin "12") (pinfunction "B_12") (pintype "input"))
      (node (ref "IC5") (pin "14") (pinfunction "CLR_14") (pintype "input"))
      (node (ref "IC5") (pin "15") (pinfunction "A_15") (pintype "input"))
      (node (ref "IC5") (pin "2") (pinfunction "CLR_2") (pintype "input"))
      (node (ref "IC5") (pin "8") (pinfunction "GND_8") (pintype "power_in"))
      (node (ref "IC6") (pin "13") (pinfunction "G_13") (pintype "input"))
      (node (ref "IC6") (pin "8") (pinfunction "GND_8") (pintype "power_in"))
      (node (ref "IC7") (pin "13") (pinfunction "G_13") (pintype "input"))
      (node (ref "IC7") (pin "8") (pinfunction "GND_8") (pintype "power_in"))
      (node (ref "IN_LF") (pin "2") (pinfunction "2_2") (pintype "passive"))
      (node (ref "J1") (pin "1@1") (pinfunction "1_1@1") (pintype "bidirectional"))
      (node (ref "J1") (pin "1@2") (pinfunction "2_1@2") (pintype "bidirectional"))
      (node (ref "PCB1") (pin "GND1") (pinfunction "GND1_GND1") (pintype "bidirectional"))
      (node (ref "PCB1") (pin "GND2") (pinfunction "GND2_GND2") (pintype "bidirectional"))
      (node (ref "PCB1") (pin "GND3") (pinfunction "GND3_GND3") (pintype "bidirectional"))
      (node (ref "PCB1") (pin "GND4") (pinfunction "GND4_GND4") (pintype "bidirectional"))
      (node (ref "R10") (pin "2") (pinfunction "2_2") (pintype "passive"))
      (node (ref "R16") (pin "1") (pinfunction "1_1") (pintype "passive"))
      (node (ref "R2") (pin "1") (pinfunction "1_1") (pintype "passive"))
      (node (ref "R20") (pin "2") (pinfunction "2_2") (pintype "passive"))
      (node (ref "R28") (pin "2") (pinfunction "2_2") (pintype "passive"))
      (node (ref "R4") (pin "3") (pinfunction "A_3") (pintype "passive"))
      (node (ref "R6") (pin "1") (pinfunction "1_1") (pintype "passive"))
      (node (ref "R8") (pin "3") (pinfunction "A_3") (pintype "passive"))
      (node (ref "REF10MHZ") (pin "2") (pinfunction "2_2") (pintype "passive"))
      (node (ref "T1") (pin "2") (pinfunction "E_2") (pintype "passive"))
      (node (ref "T10") (pin "2") (pinfunction "E_2") (pintype "passive"))
      (node (ref "T2") (pin "2") (pinfunction "E_2") (pintype "passive"))
      (node (ref "T3") (pin "2") (pinfunction "E_2") (pintype "passive"))
      (node (ref "T4") (pin "2") (pinfunction "E_2") (pintype "passive"))
      (node (ref "U1") (pin "15") (pinfunction "IN+_15") (pintype "bidirectional"))
      (node (ref "U1") (pin "16") (pinfunction "IN-_16") (pintype "bidirectional"))
      (node (ref "U1") (pin "3") (pinfunction "GND_3") (pintype "bidirectional"))
      (node (ref "U1") (pin "6") (pinfunction "VEE_6") (pintype "bidirectional"))
      (node (ref "U1") (pin "7") (pinfunction "IN+_7") (pintype "bidirectional"))
      (node (ref "U1") (pin "8") (pinfunction "IN-_8") (pintype "bidirectional"))
      (node (ref "U2") (pin "3") (pinfunction "A_3") (pintype "input"))
      (node (ref "U2") (pin "4") (pinfunction "B_4") (pintype "input"))
      (node (ref "U2") (pin "5") (pinfunction "C_5") (pintype "input"))
      (node (ref "U2") (pin "6") (pinfunction "D_6") (pintype "input"))
      (node (ref "U2") (pin "8") (pinfunction "GND_8") (pintype "power_in"))
      (node (ref "U3") (pin "4") (pinfunction "GND_4") (pintype "passive"))
      (node (ref "U3") (pin "7") (pinfunction "~{G}_7") (pintype "input"))
      (node (ref "U4") (pin "4") (pinfunction "GND_4") (pintype "bidirectional"))
      (node (ref "U6") (pin "3") (pinfunction "IN+_3") (pintype "input"))
      (node (ref "U6") (pin "4") (pinfunction "VEE_4") (pintype "bidirectional"))
      (node (ref "UART") (pin "2") (pinfunction "2_2") (pintype "passive"))
    )
    (net (code "46") (name "HF") (class "Default")
      (node (ref "PCB1") (pin "OUT") (pinfunction "OUT_OUT") (pintype "bidirectional"))
      (node (ref "U3") (pin "2") (pinfunction "B_2") (pintype "input"))
    )
    (net (code "47") (name "HFSEL1") (class "Default")
      (node (ref "IC6") (pin "6") (pinfunction "QG_6") (pintype "tri_state"))
      (node (ref "PCB1") (pin "DIVSEL1") (pinfunction "DIVSEL1_DIVSEL1") (pintype "bidirectional"))
    )
    (net (code "48") (name "HFSEL2") (class "Default")
      (node (ref "IC6") (pin "5") (pinfunction "QF_5") (pintype "tri_state"))
      (node (ref "PCB1") (pin "DIVSEL2") (pinfunction "DIVSEL2_DIVSEL2") (pintype "bidirectional"))
    )
    (net (code "49") (name "INPUTSEL") (class "Default")
      (node (ref "IC6") (pin "1") (pinfunction "QB_1") (pintype "tri_state"))
      (node (ref "U3") (pin "6") (pinfunction "~{A/B}_6") (pintype "input"))
    )
    (net (code "50") (name "I_10A") (class "Default")
      (node (ref "J3") (pin "1@1") (pinfunction "1_1@1") (pintype "bidirectional"))
      (node (ref "J3") (pin "1@2") (pinfunction "2_1@2") (pintype "bidirectional"))
      (node (ref "R16") (pin "2") (pinfunction "2_2") (pintype "passive"))
      (node (ref "R24") (pin "2") (pinfunction "2_2") (pintype "passive"))
    )
    (net (code "51") (name "I_U{slash}I{slash}R") (class "Default")
      (node (ref "J2") (pin "1@1") (pinfunction "1_1@1") (pintype "bidirectional"))
      (node (ref "J2") (pin "1@2") (pinfunction "2_1@2") (pintype "bidirectional"))
      (node (ref "K5") (pin "6") (pinfunction "P_6") (pintype "passive"))
    )
    (net (code "52") (name "LF") (class "Default")
      (node (ref "IC3") (pin "12") (pinfunction "D_12") (pintype "input"))
      (node (ref "IC3") (pin "8") (pinfunction "~{Q}_8") (pintype "output"))
      (node (ref "SJ1") (pin "1") (pinfunction "1_1") (pintype "passive"))
      (node (ref "U3") (pin "1") (pinfunction "A_1") (pintype "input"))
    )
    (net (code "53") (name "LF_DIRECT") (class "Default")
      (node (ref "IC4") (pin "14") (pinfunction "D5_14") (pintype "input"))
      (node (ref "R12") (pin "1") (pinfunction "1_1") (pintype "passive"))
    )
    (net (code "54") (name "Net-(C1-Pad1)") (class "Default")
      (node (ref "C1") (pin "1") (pinfunction "1_1") (pintype "passive"))
      (node (ref "IN_LF") (pin "1") (pinfunction "1_1") (pintype "passive"))
    )
    (net (code "55") (name "Net-(C1-Pad2)") (class "Default")
      (node (ref "C1") (pin "2") (pinfunction "2_2") (pintype "passive"))
      (node (ref "R1") (pin "1") (pinfunction "1_1") (pintype "passive"))
      (node (ref "R2") (pin "2") (pinfunction "2_2") (pintype "passive"))
      (node (ref "R3") (pin "2") (pinfunction "2_2") (pintype "passive"))
    )
    (net (code "56") (name "Net-(C3-Pad1)") (class "Default")
      (node (ref "C3") (pin "1") (pinfunction "1_1") (pintype "passive"))
      (node (ref "REF10MHZ") (pin "1") (pinfunction "1_1") (pintype "passive"))
    )
    (net (code "57") (name "Net-(C3-Pad2)") (class "Default")
      (node (ref "C3") (pin "2") (pinfunction "2_2") (pintype "passive"))
      (node (ref "R5") (pin "1") (pinfunction "1_1") (pintype "passive"))
      (node (ref "R6") (pin "2") (pinfunction "2_2") (pintype "passive"))
      (node (ref "R7") (pin "2") (pinfunction "2_2") (pintype "passive"))
    )
    (net (code "58") (name "Net-(C5-Pad2)") (class "Default")
      (node (ref "C5") (pin "2") (pinfunction "2_2") (pintype "passive"))
      (node (ref "D1") (pin "A") (pinfunction "A_A") (pintype "passive"))
      (node (ref "D2") (pin "C") (pinfunction "C_C") (pintype "passive"))
      (node (ref "R10") (pin "1") (pinfunction "1_1") (pintype "passive"))
      (node (ref "R11") (pin "2") (pinfunction "2_2") (pintype "passive"))
      (node (ref "R9") (pin "1") (pinfunction "1_1") (pintype "passive"))
    )
    (net (code "59") (name "Net-(D3-PadC)") (class "Default")
      (node (ref "D3") (pin "C") (pinfunction "C_C") (pintype "passive"))
      (node (ref "D4") (pin "A") (pinfunction "A_A") (pintype "passive"))
    )
    (net (code "60") (name "Net-(IC1A-I)") (class "Default")
      (node (ref "IC1") (pin "13") (pinfunction "I_13") (pintype "input"))
      (node (ref "R11") (pin "1") (pinfunction "1_1") (pintype "passive"))
    )
    (net (code "61") (name "Net-(IC3A-CLK)") (class "Default")
      (node (ref "IC3") (pin "3") (pinfunction "CLK_3") (pintype "input"))
      (node (ref "R12") (pin "2") (pinfunction "2_2") (pintype "passive"))
      (node (ref "U1") (pin "4") (pinfunction "OUT_4") (pintype "bidirectional"))
    )
    (net (code "62") (name "Net-(IC3A-D)") (class "Default")
      (node (ref "IC3") (pin "11") (pinfunction "CLK_11") (pintype "input"))
      (node (ref "IC3") (pin "2") (pinfunction "D_2") (pintype "input"))
      (node (ref "IC3") (pin "6") (pinfunction "~{Q}_6") (pintype "output"))
    )
    (net (code "63") (name "Net-(IC4A-D0)") (class "Default")
      (node (ref "IC4") (pin "4") (pinfunction "D0_4") (pintype "input"))
      (node (ref "U2") (pin "11") (pinfunction "QD_11") (pintype "output"))
    )
    (net (code "64") (name "Net-(IC4A-D1)") (class "Default")
      (node (ref "IC4") (pin "3") (pinfunction "D1_3") (pintype "input"))
      (node (ref "U2") (pin "12") (pinfunction "QC_12") (pintype "output"))
    )
    (net (code "65") (name "Net-(IC4A-D2)") (class "Default")
      (node (ref "IC4") (pin "2") (pinfunction "D2_2") (pintype "input"))
      (node (ref "U2") (pin "13") (pinfunction "QB_13") (pintype "output"))
    )
    (net (code "66") (name "Net-(IC4A-D3)") (class "Default")
      (node (ref "IC4") (pin "1") (pinfunction "D3_1") (pintype "input"))
      (node (ref "U2") (pin "14") (pinfunction "QA_14") (pintype "output"))
    )
    (net (code "67") (name "Net-(IC4A-D4)") (class "Default")
      (node (ref "IC4") (pin "15") (pinfunction "D4_15") (pintype "input"))
      (node (ref "R13") (pin "2") (pinfunction "2_2") (pintype "passive"))
    )
    (net (code "68") (name "Net-(IC5A-B)") (class "Default")
      (node (ref "IC5") (pin "4") (pinfunction "B_4") (pintype "input"))
      (node (ref "U1") (pin "12") (pinfunction "OUT_12") (pintype "bidirectional"))
    )
    (net (code "69") (name "Net-(IC6A-QH*)") (class "Default")
      (node (ref "IC6") (pin "9") (pinfunction "QH*_9") (pintype "tri_state"))
      (node (ref "IC7") (pin "14") (pinfunction "SER_14") (pintype "input"))
    )
    (net (code "70") (name "Net-(J4-1)") (class "Default")
      (node (ref "J4") (pin "1@1") (pinfunction "1_1@1") (pintype "bidirectional"))
      (node (ref "R9") (pin "2") (pinfunction "2_2") (pintype "passive"))
    )
    (net (code "71") (name "Net-(K1A--)") (class "Default")
      (node (ref "D11") (pin "A") (pinfunction "A_A") (pintype "passive"))
      (node (ref "D5") (pin "A") (pinfunction "A_A") (pintype "passive"))
      (node (ref "K1") (pin "8") (pinfunction "-_8") (pintype "passive"))
      (node (ref "K4") (pin "8") (pinfunction "-_8") (pintype "passive"))
      (node (ref "T3") (pin "3") (pinfunction "C_3") (pintype "passive"))
    )
    (net (code "72") (name "Net-(K1B-O)") (class "Default")
      (node (ref "K1") (pin "2") (pinfunction "O_2") (pintype "passive"))
      (node (ref "R26") (pin "1") (pinfunction "1_1") (pintype "passive"))
      (node (ref "R27") (pin "2") (pinfunction "2_2") (pintype "passive"))
    )
    (net (code "73") (name "Net-(K1B-P)") (class "Default")
      (node (ref "K1") (pin "3") (pinfunction "P_3") (pintype "passive"))
      (node (ref "K2") (pin "4") (pinfunction "S_4") (pintype "passive"))
    )
    (net (code "74") (name "Net-(K1C-O)") (class "Default")
      (node (ref "K1") (pin "7") (pinfunction "O_7") (pintype "passive"))
      (node (ref "R24") (pin "1") (pinfunction "1_1") (pintype "passive"))
      (node (ref "R25") (pin "2") (pinfunction "2_2") (pintype "passive"))
    )
    (net (code "75") (name "Net-(K1C-P)") (class "Default")
      (node (ref "K1") (pin "6") (pinfunction "P_6") (pintype "passive"))
      (node (ref "K2") (pin "2") (pinfunction "O_2") (pintype "passive"))
    )
    (net (code "76") (name "Net-(K1C-S)") (class "Default")
      (node (ref "K1") (pin "5") (pinfunction "S_5") (pintype "passive"))
      (node (ref "R25") (pin "1") (pinfunction "1_1") (pintype "passive"))
      (node (ref "R26") (pin "2") (pinfunction "2_2") (pintype "passive"))
    )
    (net (code "77") (name "Net-(K2A--)") (class "Default")
      (node (ref "D6") (pin "A") (pinfunction "A_A") (pintype "passive"))
      (node (ref "K2") (pin "8") (pinfunction "-_8") (pintype "passive"))
      (node (ref "T2") (pin "3") (pinfunction "C_3") (pintype "passive"))
    )
    (net (code "78") (name "Net-(K2C-O)") (class "Default")
      (node (ref "K2") (pin "7") (pinfunction "O_7") (pintype "passive"))
      (node (ref "K4") (pin "6") (pinfunction "P_6") (pintype "passive"))
    )
    (net (code "79") (name "Net-(K2C-S)") (class "Default")
      (node (ref "K2") (pin "5") (pinfunction "S_5") (pintype "passive"))
      (node (ref "K4") (pin "3") (pinfunction "P_3") (pintype "passive"))
    )
    (net (code "80") (name "Net-(K3A--)") (class "Default")
      (node (ref "D7") (pin "A") (pinfunction "A_A") (pintype "passive"))
      (node (ref "K3") (pin "8") (pinfunction "-_8") (pintype "passive"))
      (node (ref "T4") (pin "3") (pinfunction "C_3") (pintype "passive"))
    )
    (net (code "81") (name "Net-(K3B-P)") (class "Default")
      (node (ref "K3") (pin "3") (pinfunction "P_3") (pintype "passive"))
      (node (ref "K5") (pin "7") (pinfunction "O_7") (pintype "passive"))
    )
    (net (code "82") (name "Net-(K4B-O)") (class "Default")
      (node (ref "K4") (pin "2") (pinfunction "O_2") (pintype "passive"))
      (node (ref "R30") (pin "1") (pinfunction "1_1") (pintype "passive"))
      (node (ref "R31") (pin "2") (pinfunction "2_2") (pintype "passive"))
    )
    (net (code "83") (name "Net-(K4B-S)") (class "Default")
      (node (ref "K4") (pin "4") (pinfunction "S_4") (pintype "passive"))
      (node (ref "R31") (pin "1") (pinfunction "1_1") (pintype "passive"))
      (node (ref "R32") (pin "2") (pinfunction "2_2") (pintype "passive"))
    )
    (net (code "84") (name "Net-(K4C-O)") (class "Default")
      (node (ref "K4") (pin "7") (pinfunction "O_7") (pintype "passive"))
      (node (ref "R28") (pin "1") (pinfunction "1_1") (pintype "passive"))
      (node (ref "R29") (pin "2") (pinfunction "2_2") (pintype "passive"))
    )
    (net (code "85") (name "Net-(K4C-S)") (class "Default")
      (node (ref "K4") (pin "5") (pinfunction "S_5") (pintype "passive"))
      (node (ref "R29") (pin "1") (pinfunction "1_1") (pintype "passive"))
      (node (ref "R30") (pin "2") (pinfunction "2_2") (pintype "passive"))
    )
    (net (code "86") (name "Net-(K5A--)") (class "Default")
      (node (ref "D10") (pin "A") (pinfunction "A_A") (pintype "passive"))
      (node (ref "K5") (pin "8") (pinfunction "-_8") (pintype "passive"))
      (node (ref "T10") (pin "3") (pinfunction "C_3") (pintype "passive"))
    )
    (net (code "87") (name "Net-(K5B-S)") (class "Default")
      (node (ref "K5") (pin "4") (pinfunction "S_4") (pintype "passive"))
      (node (ref "K5") (pin "5") (pinfunction "S_5") (pintype "passive"))
      (node (ref "R37") (pin "1") (pinfunction "1_1") (pintype "passive"))
      (node (ref "R40") (pin "1") (pinfunction "1_1") (pintype "passive"))
      (node (ref "R43") (pin "1") (pinfunction "1_1") (pintype "passive"))
      (node (ref "R46") (pin "1") (pinfunction "1_1") (pintype "passive"))
      (node (ref "R49") (pin "1") (pinfunction "1_1") (pintype "passive"))
    )
    (net (code "88") (name "Net-(R4-S)") (class "Default")
      (node (ref "C2") (pin "2") (pinfunction "2_2") (pintype "passive"))
      (node (ref "R4") (pin "2") (pinfunction "S_2") (pintype "passive"))
      (node (ref "U1") (pin "1") (pinfunction "IN-_1") (pintype "bidirectional"))
    )
    (net (code "89") (name "Net-(R8-S)") (class "Default")
      (node (ref "C4") (pin "2") (pinfunction "2_2") (pintype "passive"))
      (node (ref "R8") (pin "2") (pinfunction "S_2") (pintype "passive"))
      (node (ref "U1") (pin "9") (pinfunction "IN-_9") (pintype "bidirectional"))
    )
    (net (code "90") (name "Net-(R36-Pad2)") (class "Default")
      (node (ref "R36") (pin "2") (pinfunction "2_2") (pintype "passive"))
      (node (ref "R38") (pin "1") (pinfunction "1_1") (pintype "passive"))
      (node (ref "T5") (pin "B") (pinfunction "B_B") (pintype "passive"))
    )
    (net (code "91") (name "Net-(R37-Pad2)") (class "Default")
      (node (ref "R37") (pin "2") (pinfunction "2_2") (pintype "passive"))
      (node (ref "T5") (pin "C") (pinfunction "C_C") (pintype "passive"))
    )
    (net (code "92") (name "Net-(R39-Pad2)") (class "Default")
      (node (ref "R39") (pin "2") (pinfunction "2_2") (pintype "passive"))
      (node (ref "R41") (pin "1") (pinfunction "1_1") (pintype "passive"))
      (node (ref "T6") (pin "B") (pinfunction "B_B") (pintype "passive"))
    )
    (net (code "93") (name "Net-(R40-Pad2)") (class "Default")
      (node (ref "R40") (pin "2") (pinfunction "2_2") (pintype "passive"))
      (node (ref "T6") (pin "C") (pinfunction "C_C") (pintype "passive"))
    )
    (net (code "94") (name "Net-(R42-Pad2)") (class "Default")
      (node (ref "R42") (pin "2") (pinfunction "2_2") (pintype "passive"))
      (node (ref "R44") (pin "1") (pinfunction "1_1") (pintype "passive"))
      (node (ref "T7") (pin "B") (pinfunction "B_B") (pintype "passive"))
    )
    (net (code "95") (name "Net-(R43-Pad2)") (class "Default")
      (node (ref "R43") (pin "2") (pinfunction "2_2") (pintype "passive"))
      (node (ref "T7") (pin "C") (pinfunction "C_C") (pintype "passive"))
    )
    (net (code "96") (name "Net-(R45-Pad2)") (class "Default")
      (node (ref "R45") (pin "2") (pinfunction "2_2") (pintype "passive"))
      (node (ref "R47") (pin "1") (pinfunction "1_1") (pintype "passive"))
      (node (ref "T8") (pin "B") (pinfunction "B_B") (pintype "passive"))
    )
    (net (code "97") (name "Net-(R46-Pad2)") (class "Default")
      (node (ref "R46") (pin "2") (pinfunction "2_2") (pintype "passive"))
      (node (ref "T8") (pin "C") (pinfunction "C_C") (pintype "passive"))
    )
    (net (code "98") (name "Net-(R48-Pad2)") (class "Default")
      (node (ref "R48") (pin "2") (pinfunction "2_2") (pintype "passive"))
      (node (ref "R50") (pin "1") (pinfunction "1_1") (pintype "passive"))
      (node (ref "T9") (pin "B") (pinfunction "B_B") (pintype "passive"))
    )
    (net (code "99") (name "Net-(R49-Pad2)") (class "Default")
      (node (ref "R49") (pin "2") (pinfunction "2_2") (pintype "passive"))
      (node (ref "T9") (pin "C") (pinfunction "C_C") (pintype "passive"))
    )
    (net (code "100") (name "Net-(T1-B)") (class "Default")
      (node (ref "R22") (pin "2") (pinfunction "2_2") (pintype "passive"))
      (node (ref "T1") (pin "1") (pinfunction "B_1") (pintype "passive"))
    )
    (net (code "101") (name "Net-(T2-B)") (class "Default")
      (node (ref "R33") (pin "2") (pinfunction "2_2") (pintype "passive"))
      (node (ref "T2") (pin "1") (pinfunction "B_1") (pintype "passive"))
    )
    (net (code "102") (name "Net-(T3-B)") (class "Default")
      (node (ref "R34") (pin "2") (pinfunction "2_2") (pintype "passive"))
      (node (ref "T3") (pin "1") (pinfunction "B_1") (pintype "passive"))
    )
    (net (code "103") (name "Net-(T4-B)") (class "Default")
      (node (ref "R35") (pin "2") (pinfunction "2_2") (pintype "passive"))
      (node (ref "T4") (pin "1") (pinfunction "B_1") (pintype "passive"))
    )
    (net (code "104") (name "Net-(T10-B)") (class "Default")
      (node (ref "R52") (pin "2") (pinfunction "2_2") (pintype "passive"))
      (node (ref "T10") (pin "1") (pinfunction "B_1") (pintype "passive"))
    )
    (net (code "105") (name "Net-(U1A-IN+)") (class "Default")
      (node (ref "R3") (pin "1") (pinfunction "1_1") (pintype "passive"))
      (node (ref "U1") (pin "2") (pinfunction "IN+_2") (pintype "bidirectional"))
    )
    (net (code "106") (name "Net-(U1C-IN+)") (class "Default")
      (node (ref "R7") (pin "1") (pinfunction "1_1") (pintype "passive"))
      (node (ref "U1") (pin "10") (pinfunction "IN+_10") (pintype "bidirectional"))
    )
    (net (code "107") (name "Net-(U4-C1+)") (class "Default")
      (node (ref "C14") (pin "2") (pinfunction "2_2") (pintype "passive"))
      (node (ref "U4") (pin "5") (pinfunction "C1+_5") (pintype "bidirectional"))
    )
    (net (code "108") (name "Net-(U4-C1-)") (class "Default")
      (node (ref "C14") (pin "1") (pinfunction "1_1") (pintype "passive"))
      (node (ref "U4") (pin "3") (pinfunction "C1-_3") (pintype "bidirectional"))
    )
    (net (code "109") (name "Net-(U5A-IN-)") (class "Default")
      (node (ref "R17") (pin "2") (pinfunction "2_2") (pintype "passive"))
      (node (ref "R51") (pin "2") (pinfunction "2_2") (pintype "passive"))
      (node (ref "U5") (pin "2") (pinfunction "IN-_2") (pintype "input"))
      (node (ref "U5") (pin "6") (pinfunction "OUT_6") (pintype "output"))
    )
    (net (code "110") (name "Net-(U6A-IN-)") (class "Default")
      (node (ref "R17") (pin "1") (pinfunction "1_1") (pintype "passive"))
      (node (ref "R18") (pin "2") (pinfunction "2_2") (pintype "passive"))
      (node (ref "U6") (pin "2") (pinfunction "IN-_2") (pintype "input"))
    )
    (net (code "111") (name "Net-(U6A-OUT)") (class "Default")
      (node (ref "D3") (pin "A") (pinfunction "A_A") (pintype "passive"))
      (node (ref "R22") (pin "1") (pinfunction "1_1") (pintype "passive"))
      (node (ref "U6") (pin "1") (pinfunction "OUT_1") (pintype "output"))
    )
    (net (code "112") (name "Net-(U6B-IN+)") (class "Default")
      (node (ref "D4") (pin "C") (pinfunction "C_C") (pintype "passive"))
      (node (ref "R18") (pin "1") (pinfunction "1_1") (pintype "passive"))
      (node (ref "U6") (pin "5") (pinfunction "IN+_5") (pintype "input"))
    )
    (net (code "113") (name "Net-(U6B-IN-)") (class "Default")
      (node (ref "R19") (pin "2") (pinfunction "2_2") (pintype "passive"))
      (node (ref "R20") (pin "1") (pinfunction "1_1") (pintype "passive"))
      (node (ref "U6") (pin "6") (pinfunction "IN-_6") (pintype "input"))
    )
    (net (code "114") (name "PA0") (class "Default")
      (node (ref "C16") (pin "+") (pinfunction "+_+") (pintype "passive"))
      (node (ref "DMM_RIGHT") (pin "2") (pinfunction "2_2") (pintype "passive"))
      (node (ref "R21") (pin "2") (pinfunction "2_2") (pintype "passive"))
    )
    (net (code "115") (name "PA1") (class "Default")
      (node (ref "D8") (pin "C") (pinfunction "C_C") (pintype "passive"))
      (node (ref "D9") (pin "A") (pinfunction "A_A") (pintype "passive"))
      (node (ref "DMM_RIGHT") (pin "4") (pinfunction "4_4") (pintype "passive"))
      (node (ref "R51") (pin "1") (pinfunction "1_1") (pintype "passive"))
    )
    (net (code "116") (name "PA2") (class "Default")
      (node (ref "DMM_RIGHT") (pin "6") (pinfunction "6_6") (pintype "passive"))
      (node (ref "IC6") (pin "14") (pinfunction "SER_14") (pintype "input"))
    )
    (net (code "117") (name "PB0") (class "Default")
      (node (ref "DMM_LEFT") (pin "1") (pinfunction "1_1") (pintype "passive"))
      (node (ref "R53") (pin "1") (pinfunction "1_1") (pintype "passive"))
    )
    (net (code "118") (name "PB1") (class "Default")
      (node (ref "DMM_LEFT") (pin "3") (pinfunction "3_3") (pintype "passive"))
      (node (ref "R60") (pin "1") (pinfunction "1_1") (pintype "passive"))
    )
    (net (code "119") (name "PB2") (class "Default")
      (node (ref "DMM_LEFT") (pin "5") (pinfunction "5_5") (pintype "passive"))
      (node (ref "R23") (pin "2") (pinfunction "2_2") (pintype "passive"))
      (node (ref "T1") (pin "3") (pinfunction "C_3") (pintype "passive"))
    )
    (net (code "120") (name "PD2") (class "Default")
      (node (ref "DMM_LEFT") (pin "31") (pinfunction "31_31") (pintype "passive"))
      (node (ref "R55") (pin "2") (pinfunction "2_2") (pintype "passive"))
    )
    (net (code "121") (name "PD3") (class "Default")
      (node (ref "DMM_LEFT") (pin "33") (pinfunction "33_33") (pintype "passive"))
      (node (ref "R57") (pin "2") (pinfunction "2_2") (pintype "passive"))
    )
    (net (code "122") (name "PD4") (class "Default")
      (node (ref "DMM_LEFT") (pin "35") (pinfunction "35_35") (pintype "passive"))
      (node (ref "R56") (pin "2") (pinfunction "2_2") (pintype "passive"))
    )
    (net (code "123") (name "PD5") (class "Default")
      (node (ref "DMM_LEFT") (pin "37") (pinfunction "37_37") (pintype "passive"))
      (node (ref "IC6") (pin "12") (pinfunction "RCK_12") (pintype "input"))
      (node (ref "IC7") (pin "12") (pinfunction "RCK_12") (pintype "input"))
    )
    (net (code "124") (name "PD6") (class "Default")
      (node (ref "DMM_LEFT") (pin "39") (pinfunction "39_39") (pintype "passive"))
      (node (ref "R54") (pin "1") (pinfunction "1_1") (pintype "passive"))
    )
    (net (code "125") (name "PD7") (class "Default")
      (node (ref "DMM_RIGHT") (pin "40") (pinfunction "40_40") (pintype "passive"))
      (node (ref "IC6") (pin "11") (pinfunction "SCK_11") (pintype "input"))
      (node (ref "IC7") (pin "11") (pinfunction "SCK_11") (pintype "input"))
    )
    (net (code "126") (name "RANGE_LSB") (class "Default")
      (node (ref "IC6") (pin "7") (pinfunction "QH_7") (pintype "tri_state"))
      (node (ref "R34") (pin "1") (pinfunction "1_1") (pintype "passive"))
    )
    (net (code "127") (name "RANGE_MSB") (class "Default")
      (node (ref "IC7") (pin "15") (pinfunction "QA_15") (pintype "tri_state"))
      (node (ref "R33") (pin "1") (pinfunction "1_1") (pintype "passive"))
    )
    (net (code "128") (name "R_RANGE1") (class "Default")
      (node (ref "IC7") (pin "5") (pinfunction "QF_5") (pintype "tri_state"))
      (node (ref "R36") (pin "1") (pinfunction "1_1") (pintype "passive"))
    )
    (net (code "129") (name "R_RANGE2") (class "Default")
      (node (ref "IC7") (pin "4") (pinfunction "QE_4") (pintype "tri_state"))
      (node (ref "R39") (pin "1") (pinfunction "1_1") (pintype "passive"))
    )
    (net (code "130") (name "R_RANGE3") (class "Default")
      (node (ref "IC7") (pin "3") (pinfunction "QD_3") (pintype "tri_state"))
      (node (ref "R42") (pin "1") (pinfunction "1_1") (pintype "passive"))
    )
    (net (code "131") (name "R_RANGE4") (class "Default")
      (node (ref "IC7") (pin "2") (pinfunction "QC_2") (pintype "tri_state"))
      (node (ref "R45") (pin "1") (pinfunction "1_1") (pintype "passive"))
    )
    (net (code "132") (name "R_RANGE5") (class "Default")
      (node (ref "IC7") (pin "1") (pinfunction "QB_1") (pintype "tri_state"))
      (node (ref "R48") (pin "1") (pinfunction "1_1") (pintype "passive"))
    )
    (net (code "133") (name "R_SELECTOR") (class "Default")
      (node (ref "IC7") (pin "7") (pinfunction "QH_7") (pintype "tri_state"))
      (node (ref "R52") (pin "1") (pinfunction "1_1") (pintype "passive"))
    )
    (net (code "134") (name "TTL") (class "Default")
      (node (ref "IC1") (pin "12") (pinfunction "O_12") (pintype "output"))
      (node (ref "IC4") (pin "13") (pinfunction "D6_13") (pintype "input"))
    )
    (net (code "135") (name "U_I_SELECTOR") (class "Default")
      (node (ref "IC7") (pin "6") (pinfunction "QG_6") (pintype "tri_state"))
      (node (ref "R35") (pin "1") (pinfunction "1_1") (pintype "passive"))
    )
    (net (code "136") (name "VCC") (class "Default")
      (node (ref "C10") (pin "1") (pinfunction "1_1") (pintype "passive"))
      (node (ref "C11") (pin "1") (pinfunction "1_1") (pintype "passive"))
      (node (ref "C12") (pin "1") (pinfunction "1_1") (pintype "passive"))
      (node (ref "C13") (pin "1") (pinfunction "1_1") (pintype "passive"))
      (node (ref "C17") (pin "1") (pinfunction "1_1") (pintype "passive"))
      (node (ref "C18") (pin "1") (pinfunction "1_1") (pintype "passive"))
      (node (ref "C20") (pin "+") (pinfunction "+_+") (pintype "passive"))
      (node (ref "C21") (pin "1") (pinfunction "1_1") (pintype "passive"))
      (node (ref "C22") (pin "1") (pinfunction "1_1") (pintype "passive"))
      (node (ref "C6") (pin "2") (pinfunction "2_2") (pintype "passive"))
      (node (ref "C7") (pin "1") (pinfunction "1_1") (pintype "passive"))
      (node (ref "C8") (pin "1") (pinfunction "1_1") (pintype "passive"))
      (node (ref "C9") (pin "1") (pinfunction "1_1") (pintype "passive"))
      (node (ref "D1") (pin "C") (pinfunction "C_C") (pintype "passive"))
      (node (ref "D10") (pin "C") (pinfunction "C_C") (pintype "passive"))
      (node (ref "D11") (pin "C") (pinfunction "C_C") (pintype "passive"))
      (node (ref "D5") (pin "C") (pinfunction "C_C") (pintype "passive"))
      (node (ref "D6") (pin "C") (pinfunction "C_C") (pintype "passive"))
      (node (ref "D7") (pin "C") (pinfunction "C_C") (pintype "passive"))
      (node (ref "D9") (pin "C") (pinfunction "C_C") (pintype "passive"))
      (node (ref "DMM_LEFT") (pin "19") (pinfunction "19_19") (pintype "passive"))
      (node (ref "DMM_LEFT") (pin "20") (pinfunction "20_20") (pintype "passive"))
      (node (ref "IC1") (pin "14") (pinfunction "VCC_14") (pintype "power_in"))
      (node (ref "IC2") (pin "3") (pinfunction "VIN_3") (pintype "input"))
      (node (ref "IC3") (pin "1") (pinfunction "CLR_1") (pintype "input"))
      (node (ref "IC3") (pin "10") (pinfunction "PRE_10") (pintype "input"))
      (node (ref "IC3") (pin "13") (pinfunction "CLR_13") (pintype "input"))
      (node (ref "IC3") (pin "14") (pinfunction "VCC_14") (pintype "power_in"))
      (node (ref "IC3") (pin "4") (pinfunction "PRE_4") (pintype "input"))
      (node (ref "IC4") (pin "16") (pinfunction "VCC_16") (pintype "power_in"))
      (node (ref "IC5") (pin "16") (pinfunction "VCC_16") (pintype "power_in"))
      (node (ref "IC6") (pin "10") (pinfunction "SCL_10") (pintype "input"))
      (node (ref "IC6") (pin "16") (pinfunction "VCC_16") (pintype "power_in"))
      (node (ref "IC7") (pin "10") (pinfunction "SCL_10") (pintype "input"))
      (node (ref "IC7") (pin "16") (pinfunction "VCC_16") (pintype "power_in"))
      (node (ref "K1") (pin "1") (pinfunction "+_1") (pintype "passive"))
      (node (ref "K2") (pin "1") (pinfunction "+_1") (pintype "passive"))
      (node (ref "K3") (pin "1") (pinfunction "+_1") (pintype "passive"))
      (node (ref "K4") (pin "1") (pinfunction "+_1") (pintype "passive"))
      (node (ref "K5") (pin "1") (pinfunction "+_1") (pintype "passive"))
      (node (ref "PCB1") (pin "VCC") (pinfunction "VCC_VCC") (pintype "bidirectional"))
      (node (ref "R1") (pin "2") (pinfunction "2_2") (pintype "passive"))
      (node (ref "R23") (pin "1") (pinfunction "1_1") (pintype "passive"))
      (node (ref "R4") (pin "1") (pinfunction "E_1") (pintype "passive"))
      (node (ref "R5") (pin "2") (pinfunction "2_2") (pintype "passive"))
      (node (ref "R8") (pin "1") (pinfunction "E_1") (pintype "passive"))
      (node (ref "U1") (pin "11") (pinfunction "VDD_11") (pintype "bidirectional"))
      (node (ref "U1") (pin "14") (pinfunction "VCC_14") (pintype "bidirectional"))
      (node (ref "U2") (pin "10") (pinfunction "ENT_10") (pintype "input"))
      (node (ref "U2") (pin "16") (pinfunction "VCC_16") (pintype "power_in"))
      (node (ref "U2") (pin "9") (pinfunction "~{LOAD}_9") (pintype "input"))
      (node (ref "U3") (pin "8") (pinfunction "VCC_8") (pintype "power_in"))
      (node (ref "U4") (pin "2") (pinfunction "V_IN_2") (pintype "bidirectional"))
      (node (ref "U5") (pin "7") (pinfunction "VCC_7") (pintype "bidirectional"))
      (node (ref "U6") (pin "8") (pinfunction "VCC_8") (pintype "bidirectional"))
    )
    (net (code "137") (name "unconnected-(DMM_LEFT-Pad2)") (class "Default")
      (node (ref "DMM_LEFT") (pin "2") (pinfunction "2_2") (pintype "passive"))
    )
    (net (code "138") (name "unconnected-(DMM_LEFT-Pad4)") (class "Default")
      (node (ref "DMM_LEFT") (pin "4") (pinfunction "4_4") (pintype "passive"))
    )
    (net (code "139") (name "unconnected-(DMM_LEFT-Pad6)") (class "Default")
      (node (ref "DMM_LEFT") (pin "6") (pinfunction "6_6") (pintype "passive"))
    )
    (net (code "140") (name "unconnected-(DMM_LEFT-Pad32)") (class "Default")
      (node (ref "DMM_LEFT") (pin "32") (pinfunction "32_32") (pintype "passive"))
    )
    (net (code "141") (name "unconnected-(DMM_LEFT-Pad34)") (class "Default")
      (node (ref "DMM_LEFT") (pin "34") (pinfunction "34_34") (pintype "passive"))
    )
    (net (code "142") (name "unconnected-(DMM_LEFT-Pad36)") (class "Default")
      (node (ref "DMM_LEFT") (pin "36") (pinfunction "36_36") (pintype "passive"))
    )
    (net (code "143") (name "unconnected-(DMM_LEFT-Pad38)") (class "Default")
      (node (ref "DMM_LEFT") (pin "38") (pinfunction "38_38") (pintype "passive"))
    )
    (net (code "144") (name "unconnected-(DMM_LEFT-Pad40)") (class "Default")
      (node (ref "DMM_LEFT") (pin "40") (pinfunction "40_40") (pintype "passive"))
    )
    (net (code "145") (name "unconnected-(DMM_RIGHT-Pad1)") (class "Default")
      (node (ref "DMM_RIGHT") (pin "1") (pinfunction "1_1") (pintype "passive"))
    )
    (net (code "146") (name "unconnected-(DMM_RIGHT-Pad3)") (class "Default")
      (node (ref "DMM_RIGHT") (pin "3") (pinfunction "3_3") (pintype "passive"))
    )
    (net (code "147") (name "unconnected-(DMM_RIGHT-Pad5)") (class "Default")
      (node (ref "DMM_RIGHT") (pin "5") (pinfunction "5_5") (pintype "passive"))
    )
    (net (code "148") (name "unconnected-(DMM_RIGHT-Pad39)") (class "Default")
      (node (ref "DMM_RIGHT") (pin "39") (pinfunction "39_39") (pintype "passive"))
    )
    (net (code "149") (name "unconnected-(IC1B-O-Pad10)") (class "Default")
      (node (ref "IC1") (pin "10") (pinfunction "O_10") (pintype "output"))
    )
    (net (code "150") (name "unconnected-(IC1C-O-Pad8)") (class "Default")
      (node (ref "IC1") (pin "8") (pinfunction "O_8") (pintype "output"))
    )
    (net (code "151") (name "unconnected-(IC1D-O-Pad2)") (class "Default")
      (node (ref "IC1") (pin "2") (pinfunction "O_2") (pintype "output"))
    )
    (net (code "152") (name "unconnected-(IC1E-O-Pad4)") (class "Default")
      (node (ref "IC1") (pin "4") (pinfunction "O_4") (pintype "output"))
    )
    (net (code "153") (name "unconnected-(IC1F-O-Pad6)") (class "Default")
      (node (ref "IC1") (pin "6") (pinfunction "O_6") (pintype "output"))
    )
    (net (code "154") (name "unconnected-(IC3A-Q-Pad5)") (class "Default")
      (node (ref "IC3") (pin "5") (pinfunction "Q_5") (pintype "output"))
    )
    (net (code "155") (name "unconnected-(IC3B-Q-Pad9)") (class "Default")
      (node (ref "IC3") (pin "9") (pinfunction "Q_9") (pintype "output"))
    )
    (net (code "156") (name "unconnected-(IC4A-W-Pad6)") (class "Default")
      (node (ref "IC4") (pin "6") (pinfunction "W_6") (pintype "output"))
    )
    (net (code "157") (name "unconnected-(IC5A-QA-Pad3)") (class "Default")
      (node (ref "IC5") (pin "3") (pinfunction "QA_3") (pintype "output"))
    )
    (net (code "158") (name "unconnected-(IC5A-QB-Pad5)") (class "Default")
      (node (ref "IC5") (pin "5") (pinfunction "QB_5") (pintype "output"))
    )
    (net (code "159") (name "unconnected-(IC5A-QD-Pad7)") (class "Default")
      (node (ref "IC5") (pin "7") (pinfunction "QD_7") (pintype "output"))
    )
    (net (code "160") (name "unconnected-(IC5B-QA-Pad13)") (class "Default")
      (node (ref "IC5") (pin "13") (pinfunction "QA_13") (pintype "output"))
    )
    (net (code "161") (name "unconnected-(IC5B-QB-Pad11)") (class "Default")
      (node (ref "IC5") (pin "11") (pinfunction "QB_11") (pintype "output"))
    )
    (net (code "162") (name "unconnected-(IC5B-QC-Pad10)") (class "Default")
      (node (ref "IC5") (pin "10") (pinfunction "QC_10") (pintype "output"))
    )
    (net (code "163") (name "unconnected-(IC5B-QD-Pad9)") (class "Default")
      (node (ref "IC5") (pin "9") (pinfunction "QD_9") (pintype "output"))
    )
    (net (code "164") (name "unconnected-(IC7A-QH*-Pad9)") (class "Default")
      (node (ref "IC7") (pin "9") (pinfunction "QH*_9") (pintype "tri_state"))
    )
    (net (code "165") (name "unconnected-(J4-2-Pad1@2)") (class "Default")
      (node (ref "J4") (pin "1@2") (pinfunction "2_1@2") (pintype "bidirectional"))
    )
    (net (code "166") (name "unconnected-(U1B-OUT-Pad5)") (class "Default")
      (node (ref "U1") (pin "5") (pinfunction "OUT_5") (pintype "bidirectional"))
    )
    (net (code "167") (name "unconnected-(U1D-OUT-Pad13)") (class "Default")
      (node (ref "U1") (pin "13") (pinfunction "OUT_13") (pintype "bidirectional"))
    )
    (net (code "168") (name "unconnected-(U2A-RCO-Pad15)") (class "Default")
      (node (ref "U2") (pin "15") (pinfunction "RCO_15") (pintype "output"))
    )
    (net (code "169") (name "unconnected-(U3-~{Y}-Pad3)") (class "Default")
      (node (ref "U3") (pin "3") (pinfunction "~{Y}_3") (pintype "output"))
    )
  )
)
